# LEDSubMatrixHighDensity_v2.net
KiCad netlist of a schematic drawn in EAGLE
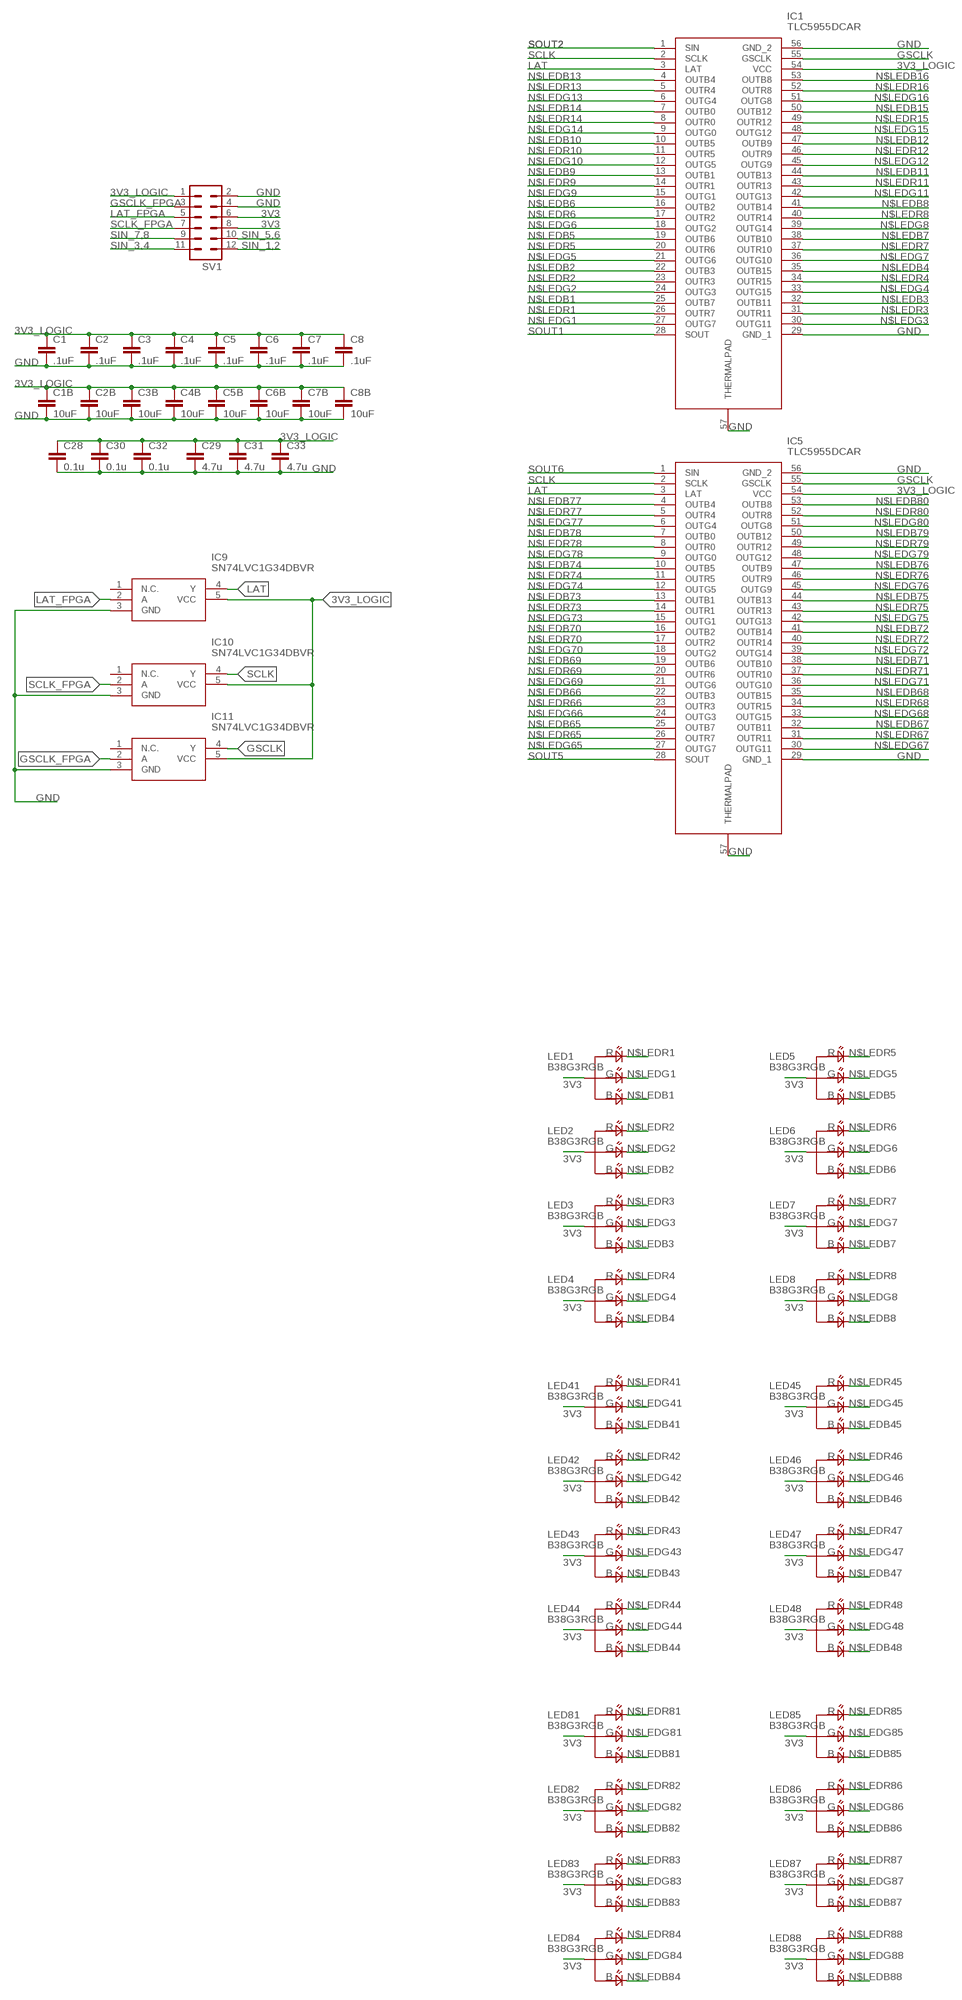
[diagram p0: schematic, sheet 1, part 1 of 2]
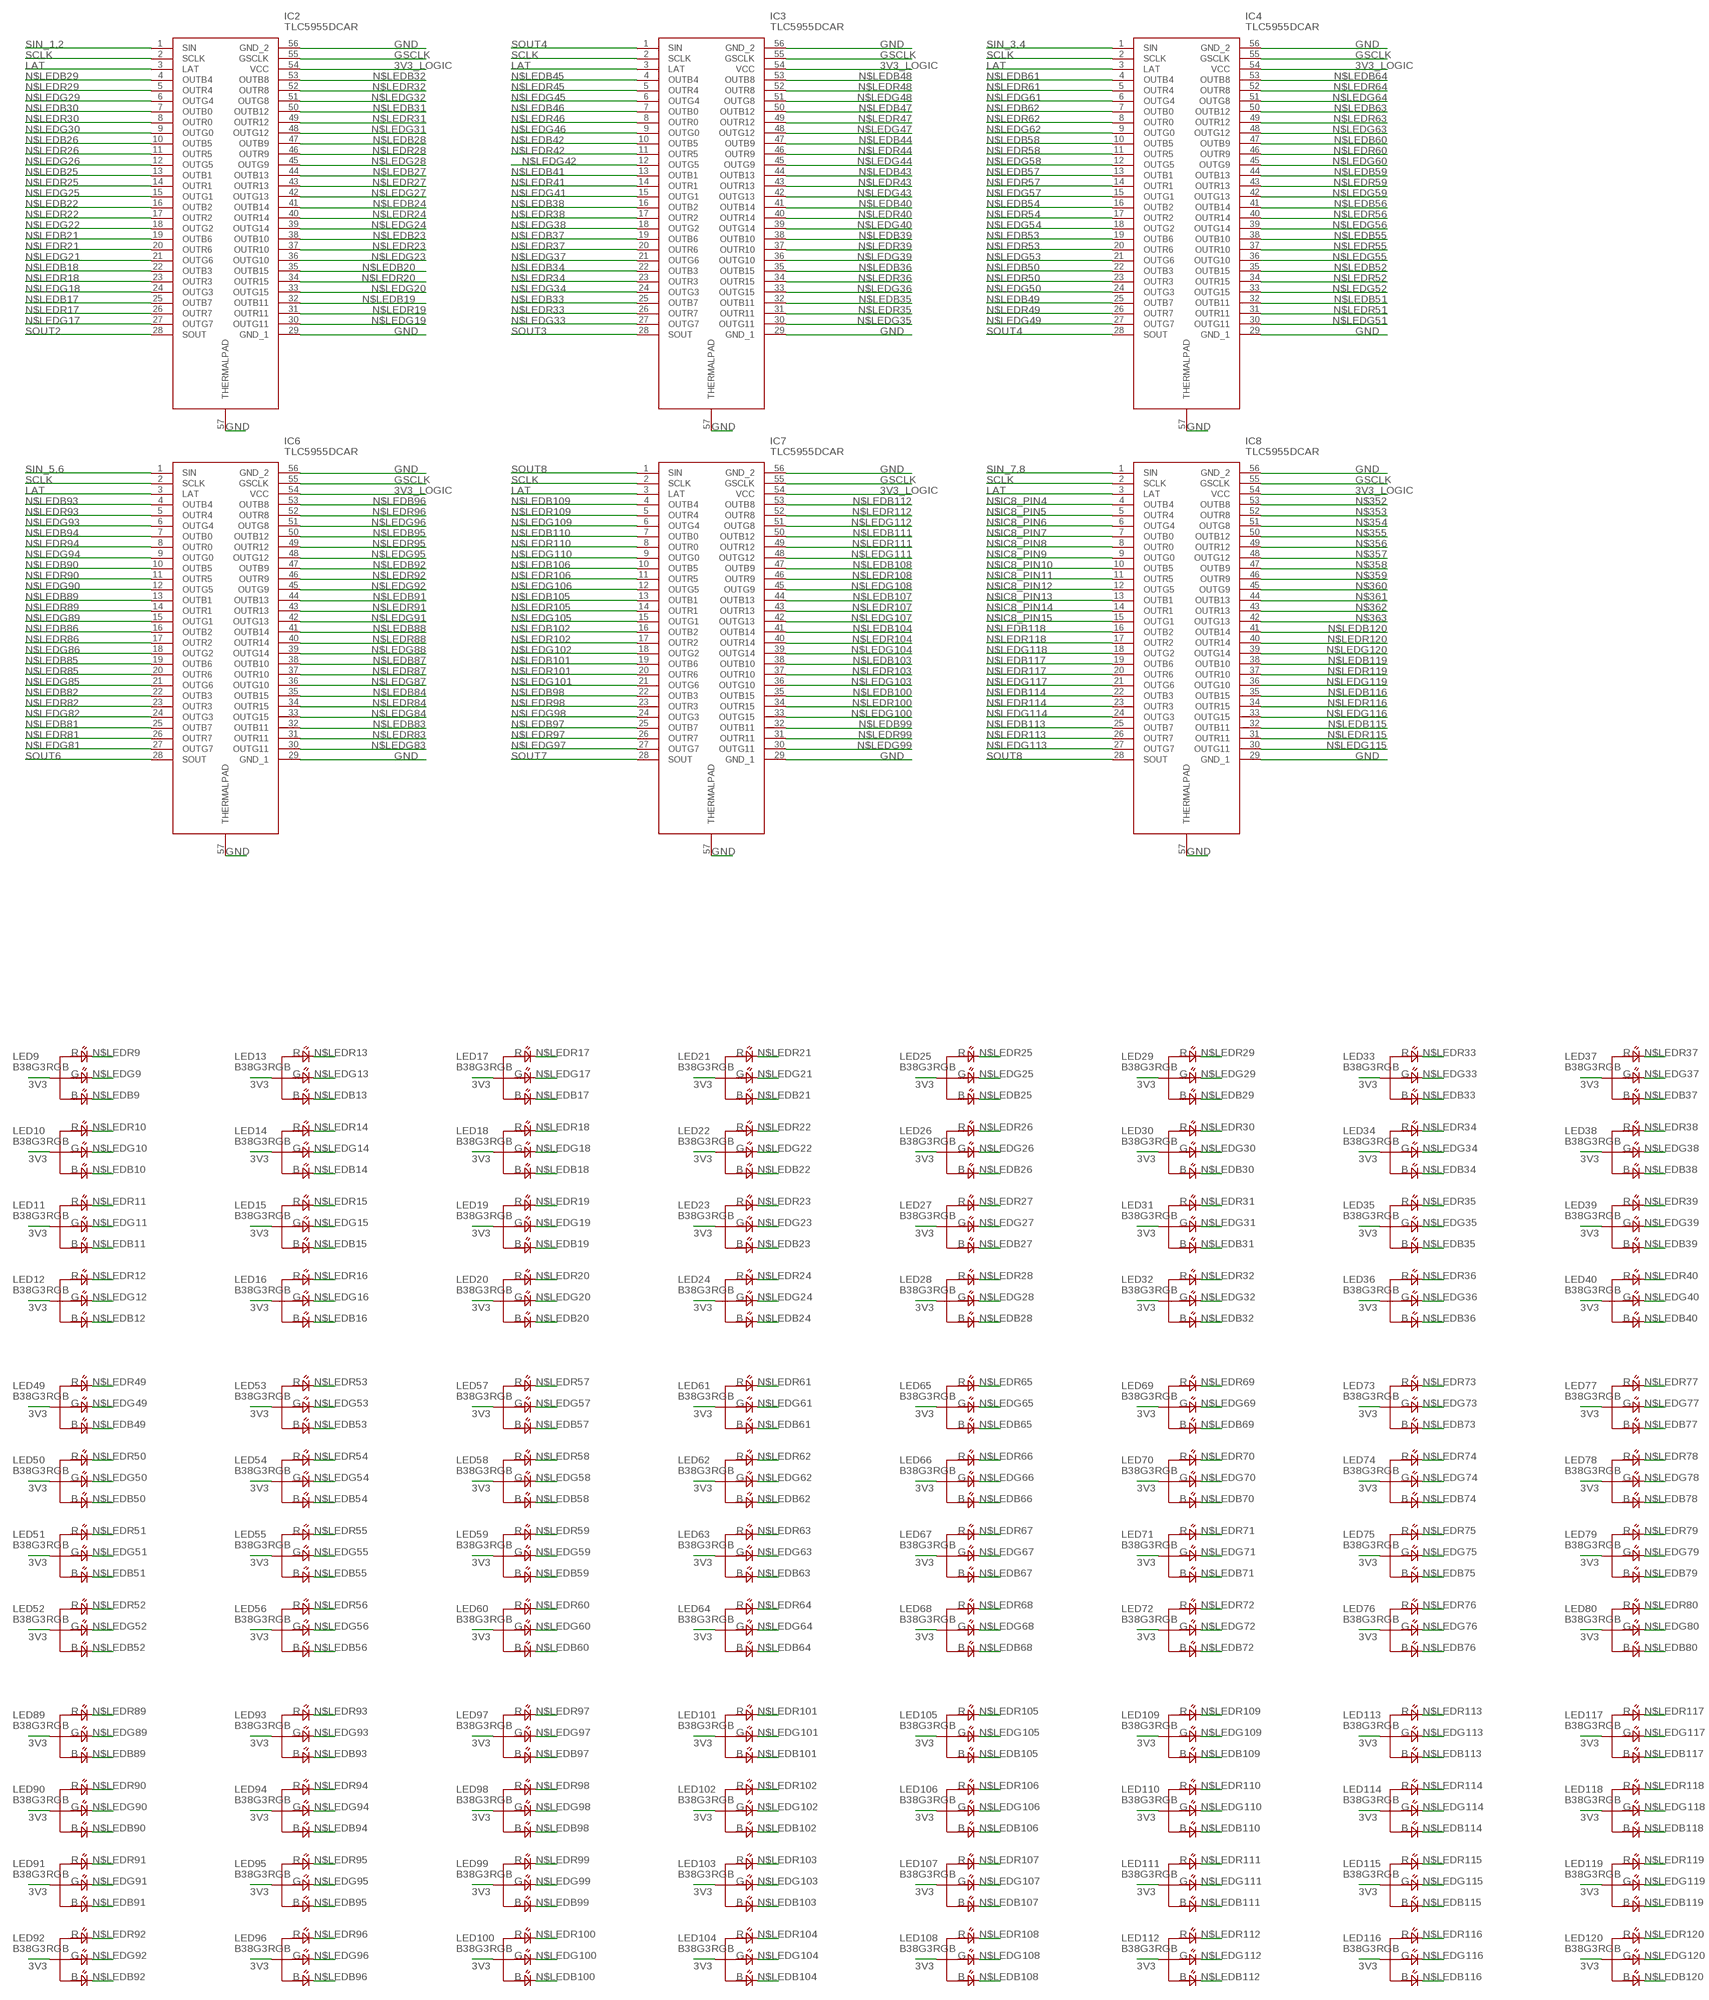
[diagram p1: schematic, sheet 1, part 2 of 2]

(export (version "E")
  (design (tool "Eeschema 10.0.6"))
  (components
    (comp (ref "C1")
      (value ".1uF")
      (footprint "eagle-import:C0402")
      (libsource (lib "eagle-import") (part "C-EUC0402"))
    )
    (comp (ref "C1B")
      (value "10uF")
      (footprint "eagle-import:C0402")
      (libsource (lib "eagle-import") (part "C-EUC0402"))
    )
    (comp (ref "C2")
      (value ".1uF")
      (footprint "eagle-import:C0402")
      (libsource (lib "eagle-import") (part "C-EUC0402"))
    )
    (comp (ref "C2B")
      (value "10uF")
      (footprint "eagle-import:C0402")
      (libsource (lib "eagle-import") (part "C-EUC0402"))
    )
    (comp (ref "C3")
      (value ".1uF")
      (footprint "eagle-import:C0402")
      (libsource (lib "eagle-import") (part "C-EUC0402"))
    )
    (comp (ref "C3B")
      (value "10uF")
      (footprint "eagle-import:C0402")
      (libsource (lib "eagle-import") (part "C-EUC0402"))
    )
    (comp (ref "C4")
      (value ".1uF")
      (footprint "eagle-import:C0402")
      (libsource (lib "eagle-import") (part "C-EUC0402"))
    )
    (comp (ref "C4B")
      (value "10uF")
      (footprint "eagle-import:C0402")
      (libsource (lib "eagle-import") (part "C-EUC0402"))
    )
    (comp (ref "C5")
      (value ".1uF")
      (footprint "eagle-import:C0402")
      (libsource (lib "eagle-import") (part "C-EUC0402"))
    )
    (comp (ref "C5B")
      (value "10uF")
      (footprint "eagle-import:C0402")
      (libsource (lib "eagle-import") (part "C-EUC0402"))
    )
    (comp (ref "C6")
      (value ".1uF")
      (footprint "eagle-import:C0402")
      (libsource (lib "eagle-import") (part "C-EUC0402"))
    )
    (comp (ref "C6B")
      (value "10uF")
      (footprint "eagle-import:C0402")
      (libsource (lib "eagle-import") (part "C-EUC0402"))
    )
    (comp (ref "C7")
      (value ".1uF")
      (footprint "eagle-import:C0402")
      (libsource (lib "eagle-import") (part "C-EUC0402"))
    )
    (comp (ref "C7B")
      (value "10uF")
      (footprint "eagle-import:C0402")
      (libsource (lib "eagle-import") (part "C-EUC0402"))
    )
    (comp (ref "C8")
      (value ".1uF")
      (footprint "eagle-import:C0402")
      (libsource (lib "eagle-import") (part "C-EUC0402"))
    )
    (comp (ref "C8B")
      (value "10uF")
      (footprint "eagle-import:C0402")
      (libsource (lib "eagle-import") (part "C-EUC0402"))
    )
    (comp (ref "C28")
      (value "0.1u")
      (footprint "eagle-import:C0402")
      (libsource (lib "eagle-import") (part "C-EUC0402"))
    )
    (comp (ref "C29")
      (value "4.7u")
      (footprint "eagle-import:C0402")
      (libsource (lib "eagle-import") (part "C-EUC0402"))
    )
    (comp (ref "C30")
      (value "0.1u")
      (footprint "eagle-import:C0402")
      (libsource (lib "eagle-import") (part "C-EUC0402"))
    )
    (comp (ref "C31")
      (value "4.7u")
      (footprint "eagle-import:C0402")
      (libsource (lib "eagle-import") (part "C-EUC0402"))
    )
    (comp (ref "C32")
      (value "0.1u")
      (footprint "eagle-import:C0402")
      (libsource (lib "eagle-import") (part "C-EUC0402"))
    )
    (comp (ref "C33")
      (value "4.7u")
      (footprint "eagle-import:C0402")
      (libsource (lib "eagle-import") (part "C-EUC0402"))
    )
    (comp (ref "IC1")
      (value "TLC5955DCAR")
      (footprint "eagle-import:SOP50P810X120-57N")
      (fields (field (name "MOUSER_PART_NUMBER") "595-TLC5955DCAR"))
      (libsource (lib "eagle-import") (part "TLC5955DCAR"))
    )
    (comp (ref "IC2")
      (value "TLC5955DCAR")
      (footprint "eagle-import:SOP50P810X120-57N")
      (fields (field (name "MOUSER_PART_NUMBER") "595-TLC5955DCAR"))
      (libsource (lib "eagle-import") (part "TLC5955DCAR"))
    )
    (comp (ref "IC3")
      (value "TLC5955DCAR")
      (footprint "eagle-import:SOP50P810X120-57N")
      (fields (field (name "MOUSER_PART_NUMBER") "595-TLC5955DCAR"))
      (libsource (lib "eagle-import") (part "TLC5955DCAR"))
    )
    (comp (ref "IC4")
      (value "TLC5955DCAR")
      (footprint "eagle-import:SOP50P810X120-57N")
      (fields (field (name "MOUSER_PART_NUMBER") "595-TLC5955DCAR"))
      (libsource (lib "eagle-import") (part "TLC5955DCAR"))
    )
    (comp (ref "IC5")
      (value "TLC5955DCAR")
      (footprint "eagle-import:SOP50P810X120-57N")
      (fields (field (name "MOUSER_PART_NUMBER") "595-TLC5955DCAR"))
      (libsource (lib "eagle-import") (part "TLC5955DCAR"))
    )
    (comp (ref "IC6")
      (value "TLC5955DCAR")
      (footprint "eagle-import:SOP50P810X120-57N")
      (fields (field (name "MOUSER_PART_NUMBER") "595-TLC5955DCAR"))
      (libsource (lib "eagle-import") (part "TLC5955DCAR"))
    )
    (comp (ref "IC7")
      (value "TLC5955DCAR")
      (footprint "eagle-import:SOP50P810X120-57N")
      (fields (field (name "MOUSER_PART_NUMBER") "595-TLC5955DCAR"))
      (libsource (lib "eagle-import") (part "TLC5955DCAR"))
    )
    (comp (ref "IC8")
      (value "TLC5955DCAR")
      (footprint "eagle-import:SOP50P810X120-57N")
      (fields (field (name "MOUSER_PART_NUMBER") "595-TLC5955DCAR"))
      (libsource (lib "eagle-import") (part "TLC5955DCAR"))
    )
    (comp (ref "IC9")
      (value "SN74LVC1G34DBVR")
      (footprint "eagle-import:SOT95P280X145-5N")
      (fields (field (name "MOUSER_PART_NUMBER") "595-SN74LVC1G34DBVR"))
      (libsource (lib "eagle-import") (part "SN74LVC1G34DBVR"))
    )
    (comp (ref "IC10")
      (value "SN74LVC1G34DBVR")
      (footprint "eagle-import:SOT95P280X145-5N")
      (fields (field (name "MOUSER_PART_NUMBER") "595-SN74LVC1G34DBVR"))
      (libsource (lib "eagle-import") (part "SN74LVC1G34DBVR"))
    )
    (comp (ref "IC11")
      (value "SN74LVC1G34DBVR")
      (footprint "eagle-import:SOT95P280X145-5N")
      (fields (field (name "MOUSER_PART_NUMBER") "595-SN74LVC1G34DBVR"))
      (libsource (lib "eagle-import") (part "SN74LVC1G34DBVR"))
    )
    (comp (ref "LED1")
      (value "B38G3RGB")
      (footprint "eagle-import:B38G3RGB")
      (fields
        (field (name "ARROW_PART_NUMBER") "SML-LX0606IGC-TR")
        (field (name "MOUSER_PART_NUMBER") "696-SML-0606IGCTR")
      )
      (libsource (lib "eagle-import") (part "B38G3RGB"))
    )
    (comp (ref "LED2")
      (value "B38G3RGB")
      (footprint "eagle-import:B38G3RGB")
      (fields
        (field (name "ARROW_PART_NUMBER") "SML-LX0606IGC-TR")
        (field (name "MOUSER_PART_NUMBER") "696-SML-0606IGCTR")
      )
      (libsource (lib "eagle-import") (part "B38G3RGB"))
    )
    (comp (ref "LED3")
      (value "B38G3RGB")
      (footprint "eagle-import:B38G3RGB")
      (fields
        (field (name "ARROW_PART_NUMBER") "SML-LX0606IGC-TR")
        (field (name "MOUSER_PART_NUMBER") "696-SML-0606IGCTR")
      )
      (libsource (lib "eagle-import") (part "B38G3RGB"))
    )
    (comp (ref "LED4")
      (value "B38G3RGB")
      (footprint "eagle-import:B38G3RGB")
      (fields
        (field (name "ARROW_PART_NUMBER") "SML-LX0606IGC-TR")
        (field (name "MOUSER_PART_NUMBER") "696-SML-0606IGCTR")
      )
      (libsource (lib "eagle-import") (part "B38G3RGB"))
    )
    (comp (ref "LED5")
      (value "B38G3RGB")
      (footprint "eagle-import:B38G3RGB")
      (fields
        (field (name "ARROW_PART_NUMBER") "SML-LX0606IGC-TR")
        (field (name "MOUSER_PART_NUMBER") "696-SML-0606IGCTR")
      )
      (libsource (lib "eagle-import") (part "B38G3RGB"))
    )
    (comp (ref "LED6")
      (value "B38G3RGB")
      (footprint "eagle-import:B38G3RGB")
      (fields
        (field (name "ARROW_PART_NUMBER") "SML-LX0606IGC-TR")
        (field (name "MOUSER_PART_NUMBER") "696-SML-0606IGCTR")
      )
      (libsource (lib "eagle-import") (part "B38G3RGB"))
    )
    (comp (ref "LED7")
      (value "B38G3RGB")
      (footprint "eagle-import:B38G3RGB")
      (fields
        (field (name "ARROW_PART_NUMBER") "SML-LX0606IGC-TR")
        (field (name "MOUSER_PART_NUMBER") "696-SML-0606IGCTR")
      )
      (libsource (lib "eagle-import") (part "B38G3RGB"))
    )
    (comp (ref "LED8")
      (value "B38G3RGB")
      (footprint "eagle-import:B38G3RGB")
      (fields
        (field (name "ARROW_PART_NUMBER") "SML-LX0606IGC-TR")
        (field (name "MOUSER_PART_NUMBER") "696-SML-0606IGCTR")
      )
      (libsource (lib "eagle-import") (part "B38G3RGB"))
    )
    (comp (ref "LED9")
      (value "B38G3RGB")
      (footprint "eagle-import:B38G3RGB")
      (fields
        (field (name "ARROW_PART_NUMBER") "SML-LX0606IGC-TR")
        (field (name "MOUSER_PART_NUMBER") "696-SML-0606IGCTR")
      )
      (libsource (lib "eagle-import") (part "B38G3RGB"))
    )
    (comp (ref "LED10")
      (value "B38G3RGB")
      (footprint "eagle-import:B38G3RGB")
      (fields
        (field (name "ARROW_PART_NUMBER") "SML-LX0606IGC-TR")
        (field (name "MOUSER_PART_NUMBER") "696-SML-0606IGCTR")
      )
      (libsource (lib "eagle-import") (part "B38G3RGB"))
    )
    (comp (ref "LED11")
      (value "B38G3RGB")
      (footprint "eagle-import:B38G3RGB")
      (fields
        (field (name "ARROW_PART_NUMBER") "SML-LX0606IGC-TR")
        (field (name "MOUSER_PART_NUMBER") "696-SML-0606IGCTR")
      )
      (libsource (lib "eagle-import") (part "B38G3RGB"))
    )
    (comp (ref "LED12")
      (value "B38G3RGB")
      (footprint "eagle-import:B38G3RGB")
      (fields
        (field (name "ARROW_PART_NUMBER") "SML-LX0606IGC-TR")
        (field (name "MOUSER_PART_NUMBER") "696-SML-0606IGCTR")
      )
      (libsource (lib "eagle-import") (part "B38G3RGB"))
    )
    (comp (ref "LED13")
      (value "B38G3RGB")
      (footprint "eagle-import:B38G3RGB")
      (fields
        (field (name "ARROW_PART_NUMBER") "SML-LX0606IGC-TR")
        (field (name "MOUSER_PART_NUMBER") "696-SML-0606IGCTR")
      )
      (libsource (lib "eagle-import") (part "B38G3RGB"))
    )
    (comp (ref "LED14")
      (value "B38G3RGB")
      (footprint "eagle-import:B38G3RGB")
      (fields
        (field (name "ARROW_PART_NUMBER") "SML-LX0606IGC-TR")
        (field (name "MOUSER_PART_NUMBER") "696-SML-0606IGCTR")
      )
      (libsource (lib "eagle-import") (part "B38G3RGB"))
    )
    (comp (ref "LED15")
      (value "B38G3RGB")
      (footprint "eagle-import:B38G3RGB")
      (fields
        (field (name "ARROW_PART_NUMBER") "SML-LX0606IGC-TR")
        (field (name "MOUSER_PART_NUMBER") "696-SML-0606IGCTR")
      )
      (libsource (lib "eagle-import") (part "B38G3RGB"))
    )
    (comp (ref "LED16")
      (value "B38G3RGB")
      (footprint "eagle-import:B38G3RGB")
      (fields
        (field (name "ARROW_PART_NUMBER") "SML-LX0606IGC-TR")
        (field (name "MOUSER_PART_NUMBER") "696-SML-0606IGCTR")
      )
      (libsource (lib "eagle-import") (part "B38G3RGB"))
    )
    (comp (ref "LED17")
      (value "B38G3RGB")
      (footprint "eagle-import:B38G3RGB")
      (fields
        (field (name "ARROW_PART_NUMBER") "SML-LX0606IGC-TR")
        (field (name "MOUSER_PART_NUMBER") "696-SML-0606IGCTR")
      )
      (libsource (lib "eagle-import") (part "B38G3RGB"))
    )
    (comp (ref "LED18")
      (value "B38G3RGB")
      (footprint "eagle-import:B38G3RGB")
      (fields
        (field (name "ARROW_PART_NUMBER") "SML-LX0606IGC-TR")
        (field (name "MOUSER_PART_NUMBER") "696-SML-0606IGCTR")
      )
      (libsource (lib "eagle-import") (part "B38G3RGB"))
    )
    (comp (ref "LED19")
      (value "B38G3RGB")
      (footprint "eagle-import:B38G3RGB")
      (fields
        (field (name "ARROW_PART_NUMBER") "SML-LX0606IGC-TR")
        (field (name "MOUSER_PART_NUMBER") "696-SML-0606IGCTR")
      )
      (libsource (lib "eagle-import") (part "B38G3RGB"))
    )
    (comp (ref "LED20")
      (value "B38G3RGB")
      (footprint "eagle-import:B38G3RGB")
      (fields
        (field (name "ARROW_PART_NUMBER") "SML-LX0606IGC-TR")
        (field (name "MOUSER_PART_NUMBER") "696-SML-0606IGCTR")
      )
      (libsource (lib "eagle-import") (part "B38G3RGB"))
    )
    (comp (ref "LED21")
      (value "B38G3RGB")
      (footprint "eagle-import:B38G3RGB")
      (fields
        (field (name "ARROW_PART_NUMBER") "SML-LX0606IGC-TR")
        (field (name "MOUSER_PART_NUMBER") "696-SML-0606IGCTR")
      )
      (libsource (lib "eagle-import") (part "B38G3RGB"))
    )
    (comp (ref "LED22")
      (value "B38G3RGB")
      (footprint "eagle-import:B38G3RGB")
      (fields
        (field (name "ARROW_PART_NUMBER") "SML-LX0606IGC-TR")
        (field (name "MOUSER_PART_NUMBER") "696-SML-0606IGCTR")
      )
      (libsource (lib "eagle-import") (part "B38G3RGB"))
    )
    (comp (ref "LED23")
      (value "B38G3RGB")
      (footprint "eagle-import:B38G3RGB")
      (fields
        (field (name "ARROW_PART_NUMBER") "SML-LX0606IGC-TR")
        (field (name "MOUSER_PART_NUMBER") "696-SML-0606IGCTR")
      )
      (libsource (lib "eagle-import") (part "B38G3RGB"))
    )
    (comp (ref "LED24")
      (value "B38G3RGB")
      (footprint "eagle-import:B38G3RGB")
      (fields
        (field (name "ARROW_PART_NUMBER") "SML-LX0606IGC-TR")
        (field (name "MOUSER_PART_NUMBER") "696-SML-0606IGCTR")
      )
      (libsource (lib "eagle-import") (part "B38G3RGB"))
    )
    (comp (ref "LED25")
      (value "B38G3RGB")
      (footprint "eagle-import:B38G3RGB")
      (fields
        (field (name "ARROW_PART_NUMBER") "SML-LX0606IGC-TR")
        (field (name "MOUSER_PART_NUMBER") "696-SML-0606IGCTR")
      )
      (libsource (lib "eagle-import") (part "B38G3RGB"))
    )
    (comp (ref "LED26")
      (value "B38G3RGB")
      (footprint "eagle-import:B38G3RGB")
      (fields
        (field (name "ARROW_PART_NUMBER") "SML-LX0606IGC-TR")
        (field (name "MOUSER_PART_NUMBER") "696-SML-0606IGCTR")
      )
      (libsource (lib "eagle-import") (part "B38G3RGB"))
    )
    (comp (ref "LED27")
      (value "B38G3RGB")
      (footprint "eagle-import:B38G3RGB")
      (fields
        (field (name "ARROW_PART_NUMBER") "SML-LX0606IGC-TR")
        (field (name "MOUSER_PART_NUMBER") "696-SML-0606IGCTR")
      )
      (libsource (lib "eagle-import") (part "B38G3RGB"))
    )
    (comp (ref "LED28")
      (value "B38G3RGB")
      (footprint "eagle-import:B38G3RGB")
      (fields
        (field (name "ARROW_PART_NUMBER") "SML-LX0606IGC-TR")
        (field (name "MOUSER_PART_NUMBER") "696-SML-0606IGCTR")
      )
      (libsource (lib "eagle-import") (part "B38G3RGB"))
    )
    (comp (ref "LED29")
      (value "B38G3RGB")
      (footprint "eagle-import:B38G3RGB")
      (fields
        (field (name "ARROW_PART_NUMBER") "SML-LX0606IGC-TR")
        (field (name "MOUSER_PART_NUMBER") "696-SML-0606IGCTR")
      )
      (libsource (lib "eagle-import") (part "B38G3RGB"))
    )
    (comp (ref "LED30")
      (value "B38G3RGB")
      (footprint "eagle-import:B38G3RGB")
      (fields
        (field (name "ARROW_PART_NUMBER") "SML-LX0606IGC-TR")
        (field (name "MOUSER_PART_NUMBER") "696-SML-0606IGCTR")
      )
      (libsource (lib "eagle-import") (part "B38G3RGB"))
    )
    (comp (ref "LED31")
      (value "B38G3RGB")
      (footprint "eagle-import:B38G3RGB")
      (fields
        (field (name "ARROW_PART_NUMBER") "SML-LX0606IGC-TR")
        (field (name "MOUSER_PART_NUMBER") "696-SML-0606IGCTR")
      )
      (libsource (lib "eagle-import") (part "B38G3RGB"))
    )
    (comp (ref "LED32")
      (value "B38G3RGB")
      (footprint "eagle-import:B38G3RGB")
      (fields
        (field (name "ARROW_PART_NUMBER") "SML-LX0606IGC-TR")
        (field (name "MOUSER_PART_NUMBER") "696-SML-0606IGCTR")
      )
      (libsource (lib "eagle-import") (part "B38G3RGB"))
    )
    (comp (ref "LED33")
      (value "B38G3RGB")
      (footprint "eagle-import:B38G3RGB")
      (fields
        (field (name "ARROW_PART_NUMBER") "SML-LX0606IGC-TR")
        (field (name "MOUSER_PART_NUMBER") "696-SML-0606IGCTR")
      )
      (libsource (lib "eagle-import") (part "B38G3RGB"))
    )
    (comp (ref "LED34")
      (value "B38G3RGB")
      (footprint "eagle-import:B38G3RGB")
      (fields
        (field (name "ARROW_PART_NUMBER") "SML-LX0606IGC-TR")
        (field (name "MOUSER_PART_NUMBER") "696-SML-0606IGCTR")
      )
      (libsource (lib "eagle-import") (part "B38G3RGB"))
    )
    (comp (ref "LED35")
      (value "B38G3RGB")
      (footprint "eagle-import:B38G3RGB")
      (fields
        (field (name "ARROW_PART_NUMBER") "SML-LX0606IGC-TR")
        (field (name "MOUSER_PART_NUMBER") "696-SML-0606IGCTR")
      )
      (libsource (lib "eagle-import") (part "B38G3RGB"))
    )
    (comp (ref "LED36")
      (value "B38G3RGB")
      (footprint "eagle-import:B38G3RGB")
      (fields
        (field (name "ARROW_PART_NUMBER") "SML-LX0606IGC-TR")
        (field (name "MOUSER_PART_NUMBER") "696-SML-0606IGCTR")
      )
      (libsource (lib "eagle-import") (part "B38G3RGB"))
    )
    (comp (ref "LED37")
      (value "B38G3RGB")
      (footprint "eagle-import:B38G3RGB")
      (fields
        (field (name "ARROW_PART_NUMBER") "SML-LX0606IGC-TR")
        (field (name "MOUSER_PART_NUMBER") "696-SML-0606IGCTR")
      )
      (libsource (lib "eagle-import") (part "B38G3RGB"))
    )
    (comp (ref "LED38")
      (value "B38G3RGB")
      (footprint "eagle-import:B38G3RGB")
      (fields
        (field (name "ARROW_PART_NUMBER") "SML-LX0606IGC-TR")
        (field (name "MOUSER_PART_NUMBER") "696-SML-0606IGCTR")
      )
      (libsource (lib "eagle-import") (part "B38G3RGB"))
    )
    (comp (ref "LED39")
      (value "B38G3RGB")
      (footprint "eagle-import:B38G3RGB")
      (fields
        (field (name "ARROW_PART_NUMBER") "SML-LX0606IGC-TR")
        (field (name "MOUSER_PART_NUMBER") "696-SML-0606IGCTR")
      )
      (libsource (lib "eagle-import") (part "B38G3RGB"))
    )
    (comp (ref "LED40")
      (value "B38G3RGB")
      (footprint "eagle-import:B38G3RGB")
      (fields
        (field (name "ARROW_PART_NUMBER") "SML-LX0606IGC-TR")
        (field (name "MOUSER_PART_NUMBER") "696-SML-0606IGCTR")
      )
      (libsource (lib "eagle-import") (part "B38G3RGB"))
    )
    (comp (ref "LED41")
      (value "B38G3RGB")
      (footprint "eagle-import:B38G3RGB")
      (fields
        (field (name "ARROW_PART_NUMBER") "SML-LX0606IGC-TR")
        (field (name "MOUSER_PART_NUMBER") "696-SML-0606IGCTR")
      )
      (libsource (lib "eagle-import") (part "B38G3RGB"))
    )
    (comp (ref "LED42")
      (value "B38G3RGB")
      (footprint "eagle-import:B38G3RGB")
      (fields
        (field (name "ARROW_PART_NUMBER") "SML-LX0606IGC-TR")
        (field (name "MOUSER_PART_NUMBER") "696-SML-0606IGCTR")
      )
      (libsource (lib "eagle-import") (part "B38G3RGB"))
    )
    (comp (ref "LED43")
      (value "B38G3RGB")
      (footprint "eagle-import:B38G3RGB")
      (fields
        (field (name "ARROW_PART_NUMBER") "SML-LX0606IGC-TR")
        (field (name "MOUSER_PART_NUMBER") "696-SML-0606IGCTR")
      )
      (libsource (lib "eagle-import") (part "B38G3RGB"))
    )
    (comp (ref "LED44")
      (value "B38G3RGB")
      (footprint "eagle-import:B38G3RGB")
      (fields
        (field (name "ARROW_PART_NUMBER") "SML-LX0606IGC-TR")
        (field (name "MOUSER_PART_NUMBER") "696-SML-0606IGCTR")
      )
      (libsource (lib "eagle-import") (part "B38G3RGB"))
    )
    (comp (ref "LED45")
      (value "B38G3RGB")
      (footprint "eagle-import:B38G3RGB")
      (fields
        (field (name "ARROW_PART_NUMBER") "SML-LX0606IGC-TR")
        (field (name "MOUSER_PART_NUMBER") "696-SML-0606IGCTR")
      )
      (libsource (lib "eagle-import") (part "B38G3RGB"))
    )
    (comp (ref "LED46")
      (value "B38G3RGB")
      (footprint "eagle-import:B38G3RGB")
      (fields
        (field (name "ARROW_PART_NUMBER") "SML-LX0606IGC-TR")
        (field (name "MOUSER_PART_NUMBER") "696-SML-0606IGCTR")
      )
      (libsource (lib "eagle-import") (part "B38G3RGB"))
    )
    (comp (ref "LED47")
      (value "B38G3RGB")
      (footprint "eagle-import:B38G3RGB")
      (fields
        (field (name "ARROW_PART_NUMBER") "SML-LX0606IGC-TR")
        (field (name "MOUSER_PART_NUMBER") "696-SML-0606IGCTR")
      )
      (libsource (lib "eagle-import") (part "B38G3RGB"))
    )
    (comp (ref "LED48")
      (value "B38G3RGB")
      (footprint "eagle-import:B38G3RGB")
      (fields
        (field (name "ARROW_PART_NUMBER") "SML-LX0606IGC-TR")
        (field (name "MOUSER_PART_NUMBER") "696-SML-0606IGCTR")
      )
      (libsource (lib "eagle-import") (part "B38G3RGB"))
    )
    (comp (ref "LED49")
      (value "B38G3RGB")
      (footprint "eagle-import:B38G3RGB")
      (fields
        (field (name "ARROW_PART_NUMBER") "SML-LX0606IGC-TR")
        (field (name "MOUSER_PART_NUMBER") "696-SML-0606IGCTR")
      )
      (libsource (lib "eagle-import") (part "B38G3RGB"))
    )
    (comp (ref "LED50")
      (value "B38G3RGB")
      (footprint "eagle-import:B38G3RGB")
      (fields
        (field (name "ARROW_PART_NUMBER") "SML-LX0606IGC-TR")
        (field (name "MOUSER_PART_NUMBER") "696-SML-0606IGCTR")
      )
      (libsource (lib "eagle-import") (part "B38G3RGB"))
    )
    (comp (ref "LED51")
      (value "B38G3RGB")
      (footprint "eagle-import:B38G3RGB")
      (fields
        (field (name "ARROW_PART_NUMBER") "SML-LX0606IGC-TR")
        (field (name "MOUSER_PART_NUMBER") "696-SML-0606IGCTR")
      )
      (libsource (lib "eagle-import") (part "B38G3RGB"))
    )
    (comp (ref "LED52")
      (value "B38G3RGB")
      (footprint "eagle-import:B38G3RGB")
      (fields
        (field (name "ARROW_PART_NUMBER") "SML-LX0606IGC-TR")
        (field (name "MOUSER_PART_NUMBER") "696-SML-0606IGCTR")
      )
      (libsource (lib "eagle-import") (part "B38G3RGB"))
    )
    (comp (ref "LED53")
      (value "B38G3RGB")
      (footprint "eagle-import:B38G3RGB")
      (fields
        (field (name "ARROW_PART_NUMBER") "SML-LX0606IGC-TR")
        (field (name "MOUSER_PART_NUMBER") "696-SML-0606IGCTR")
      )
      (libsource (lib "eagle-import") (part "B38G3RGB"))
    )
    (comp (ref "LED54")
      (value "B38G3RGB")
      (footprint "eagle-import:B38G3RGB")
      (fields
        (field (name "ARROW_PART_NUMBER") "SML-LX0606IGC-TR")
        (field (name "MOUSER_PART_NUMBER") "696-SML-0606IGCTR")
      )
      (libsource (lib "eagle-import") (part "B38G3RGB"))
    )
    (comp (ref "LED55")
      (value "B38G3RGB")
      (footprint "eagle-import:B38G3RGB")
      (fields
        (field (name "ARROW_PART_NUMBER") "SML-LX0606IGC-TR")
        (field (name "MOUSER_PART_NUMBER") "696-SML-0606IGCTR")
      )
      (libsource (lib "eagle-import") (part "B38G3RGB"))
    )
    (comp (ref "LED56")
      (value "B38G3RGB")
      (footprint "eagle-import:B38G3RGB")
      (fields
        (field (name "ARROW_PART_NUMBER") "SML-LX0606IGC-TR")
        (field (name "MOUSER_PART_NUMBER") "696-SML-0606IGCTR")
      )
      (libsource (lib "eagle-import") (part "B38G3RGB"))
    )
    (comp (ref "LED57")
      (value "B38G3RGB")
      (footprint "eagle-import:B38G3RGB")
      (fields
        (field (name "ARROW_PART_NUMBER") "SML-LX0606IGC-TR")
        (field (name "MOUSER_PART_NUMBER") "696-SML-0606IGCTR")
      )
      (libsource (lib "eagle-import") (part "B38G3RGB"))
    )
    (comp (ref "LED58")
      (value "B38G3RGB")
      (footprint "eagle-import:B38G3RGB")
      (fields
        (field (name "ARROW_PART_NUMBER") "SML-LX0606IGC-TR")
        (field (name "MOUSER_PART_NUMBER") "696-SML-0606IGCTR")
      )
      (libsource (lib "eagle-import") (part "B38G3RGB"))
    )
    (comp (ref "LED59")
      (value "B38G3RGB")
      (footprint "eagle-import:B38G3RGB")
      (fields
        (field (name "ARROW_PART_NUMBER") "SML-LX0606IGC-TR")
        (field (name "MOUSER_PART_NUMBER") "696-SML-0606IGCTR")
      )
      (libsource (lib "eagle-import") (part "B38G3RGB"))
    )
    (comp (ref "LED60")
      (value "B38G3RGB")
      (footprint "eagle-import:B38G3RGB")
      (fields
        (field (name "ARROW_PART_NUMBER") "SML-LX0606IGC-TR")
        (field (name "MOUSER_PART_NUMBER") "696-SML-0606IGCTR")
      )
      (libsource (lib "eagle-import") (part "B38G3RGB"))
    )
    (comp (ref "LED61")
      (value "B38G3RGB")
      (footprint "eagle-import:B38G3RGB")
      (fields
        (field (name "ARROW_PART_NUMBER") "SML-LX0606IGC-TR")
        (field (name "MOUSER_PART_NUMBER") "696-SML-0606IGCTR")
      )
      (libsource (lib "eagle-import") (part "B38G3RGB"))
    )
    (comp (ref "LED62")
      (value "B38G3RGB")
      (footprint "eagle-import:B38G3RGB")
      (fields
        (field (name "ARROW_PART_NUMBER") "SML-LX0606IGC-TR")
        (field (name "MOUSER_PART_NUMBER") "696-SML-0606IGCTR")
      )
      (libsource (lib "eagle-import") (part "B38G3RGB"))
    )
    (comp (ref "LED63")
      (value "B38G3RGB")
      (footprint "eagle-import:B38G3RGB")
      (fields
        (field (name "ARROW_PART_NUMBER") "SML-LX0606IGC-TR")
        (field (name "MOUSER_PART_NUMBER") "696-SML-0606IGCTR")
      )
      (libsource (lib "eagle-import") (part "B38G3RGB"))
    )
    (comp (ref "LED64")
      (value "B38G3RGB")
      (footprint "eagle-import:B38G3RGB")
      (fields
        (field (name "ARROW_PART_NUMBER") "SML-LX0606IGC-TR")
        (field (name "MOUSER_PART_NUMBER") "696-SML-0606IGCTR")
      )
      (libsource (lib "eagle-import") (part "B38G3RGB"))
    )
    (comp (ref "LED65")
      (value "B38G3RGB")
      (footprint "eagle-import:B38G3RGB")
      (fields
        (field (name "ARROW_PART_NUMBER") "SML-LX0606IGC-TR")
        (field (name "MOUSER_PART_NUMBER") "696-SML-0606IGCTR")
      )
      (libsource (lib "eagle-import") (part "B38G3RGB"))
    )
    (comp (ref "LED66")
      (value "B38G3RGB")
      (footprint "eagle-import:B38G3RGB")
      (fields
        (field (name "ARROW_PART_NUMBER") "SML-LX0606IGC-TR")
        (field (name "MOUSER_PART_NUMBER") "696-SML-0606IGCTR")
      )
      (libsource (lib "eagle-import") (part "B38G3RGB"))
    )
    (comp (ref "LED67")
      (value "B38G3RGB")
      (footprint "eagle-import:B38G3RGB")
      (fields
        (field (name "ARROW_PART_NUMBER") "SML-LX0606IGC-TR")
        (field (name "MOUSER_PART_NUMBER") "696-SML-0606IGCTR")
      )
      (libsource (lib "eagle-import") (part "B38G3RGB"))
    )
    (comp (ref "LED68")
      (value "B38G3RGB")
      (footprint "eagle-import:B38G3RGB")
      (fields
        (field (name "ARROW_PART_NUMBER") "SML-LX0606IGC-TR")
        (field (name "MOUSER_PART_NUMBER") "696-SML-0606IGCTR")
      )
      (libsource (lib "eagle-import") (part "B38G3RGB"))
    )
    (comp (ref "LED69")
      (value "B38G3RGB")
      (footprint "eagle-import:B38G3RGB")
      (fields
        (field (name "ARROW_PART_NUMBER") "SML-LX0606IGC-TR")
        (field (name "MOUSER_PART_NUMBER") "696-SML-0606IGCTR")
      )
      (libsource (lib "eagle-import") (part "B38G3RGB"))
    )
    (comp (ref "LED70")
      (value "B38G3RGB")
      (footprint "eagle-import:B38G3RGB")
      (fields
        (field (name "ARROW_PART_NUMBER") "SML-LX0606IGC-TR")
        (field (name "MOUSER_PART_NUMBER") "696-SML-0606IGCTR")
      )
      (libsource (lib "eagle-import") (part "B38G3RGB"))
    )
    (comp (ref "LED71")
      (value "B38G3RGB")
      (footprint "eagle-import:B38G3RGB")
      (fields
        (field (name "ARROW_PART_NUMBER") "SML-LX0606IGC-TR")
        (field (name "MOUSER_PART_NUMBER") "696-SML-0606IGCTR")
      )
      (libsource (lib "eagle-import") (part "B38G3RGB"))
    )
    (comp (ref "LED72")
      (value "B38G3RGB")
      (footprint "eagle-import:B38G3RGB")
      (fields
        (field (name "ARROW_PART_NUMBER") "SML-LX0606IGC-TR")
        (field (name "MOUSER_PART_NUMBER") "696-SML-0606IGCTR")
      )
      (libsource (lib "eagle-import") (part "B38G3RGB"))
    )
    (comp (ref "LED73")
      (value "B38G3RGB")
      (footprint "eagle-import:B38G3RGB")
      (fields
        (field (name "ARROW_PART_NUMBER") "SML-LX0606IGC-TR")
        (field (name "MOUSER_PART_NUMBER") "696-SML-0606IGCTR")
      )
      (libsource (lib "eagle-import") (part "B38G3RGB"))
    )
    (comp (ref "LED74")
      (value "B38G3RGB")
      (footprint "eagle-import:B38G3RGB")
      (fields
        (field (name "ARROW_PART_NUMBER") "SML-LX0606IGC-TR")
        (field (name "MOUSER_PART_NUMBER") "696-SML-0606IGCTR")
      )
      (libsource (lib "eagle-import") (part "B38G3RGB"))
    )
    (comp (ref "LED75")
      (value "B38G3RGB")
      (footprint "eagle-import:B38G3RGB")
      (fields
        (field (name "ARROW_PART_NUMBER") "SML-LX0606IGC-TR")
        (field (name "MOUSER_PART_NUMBER") "696-SML-0606IGCTR")
      )
      (libsource (lib "eagle-import") (part "B38G3RGB"))
    )
    (comp (ref "LED76")
      (value "B38G3RGB")
      (footprint "eagle-import:B38G3RGB")
      (fields
        (field (name "ARROW_PART_NUMBER") "SML-LX0606IGC-TR")
        (field (name "MOUSER_PART_NUMBER") "696-SML-0606IGCTR")
      )
      (libsource (lib "eagle-import") (part "B38G3RGB"))
    )
    (comp (ref "LED77")
      (value "B38G3RGB")
      (footprint "eagle-import:B38G3RGB")
      (fields
        (field (name "ARROW_PART_NUMBER") "SML-LX0606IGC-TR")
        (field (name "MOUSER_PART_NUMBER") "696-SML-0606IGCTR")
      )
      (libsource (lib "eagle-import") (part "B38G3RGB"))
    )
    (comp (ref "LED78")
      (value "B38G3RGB")
      (footprint "eagle-import:B38G3RGB")
      (fields
        (field (name "ARROW_PART_NUMBER") "SML-LX0606IGC-TR")
        (field (name "MOUSER_PART_NUMBER") "696-SML-0606IGCTR")
      )
      (libsource (lib "eagle-import") (part "B38G3RGB"))
    )
    (comp (ref "LED79")
      (value "B38G3RGB")
      (footprint "eagle-import:B38G3RGB")
      (fields
        (field (name "ARROW_PART_NUMBER") "SML-LX0606IGC-TR")
        (field (name "MOUSER_PART_NUMBER") "696-SML-0606IGCTR")
      )
      (libsource (lib "eagle-import") (part "B38G3RGB"))
    )
    (comp (ref "LED80")
      (value "B38G3RGB")
      (footprint "eagle-import:B38G3RGB")
      (fields
        (field (name "ARROW_PART_NUMBER") "SML-LX0606IGC-TR")
        (field (name "MOUSER_PART_NUMBER") "696-SML-0606IGCTR")
      )
      (libsource (lib "eagle-import") (part "B38G3RGB"))
    )
    (comp (ref "LED81")
      (value "B38G3RGB")
      (footprint "eagle-import:B38G3RGB")
      (fields
        (field (name "ARROW_PART_NUMBER") "SML-LX0606IGC-TR")
        (field (name "MOUSER_PART_NUMBER") "696-SML-0606IGCTR")
      )
      (libsource (lib "eagle-import") (part "B38G3RGB"))
    )
    (comp (ref "LED82")
      (value "B38G3RGB")
      (footprint "eagle-import:B38G3RGB")
      (fields
        (field (name "ARROW_PART_NUMBER") "SML-LX0606IGC-TR")
        (field (name "MOUSER_PART_NUMBER") "696-SML-0606IGCTR")
      )
      (libsource (lib "eagle-import") (part "B38G3RGB"))
    )
    (comp (ref "LED83")
      (value "B38G3RGB")
      (footprint "eagle-import:B38G3RGB")
      (fields
        (field (name "ARROW_PART_NUMBER") "SML-LX0606IGC-TR")
        (field (name "MOUSER_PART_NUMBER") "696-SML-0606IGCTR")
      )
      (libsource (lib "eagle-import") (part "B38G3RGB"))
    )
    (comp (ref "LED84")
      (value "B38G3RGB")
      (footprint "eagle-import:B38G3RGB")
      (fields
        (field (name "ARROW_PART_NUMBER") "SML-LX0606IGC-TR")
        (field (name "MOUSER_PART_NUMBER") "696-SML-0606IGCTR")
      )
      (libsource (lib "eagle-import") (part "B38G3RGB"))
    )
    (comp (ref "LED85")
      (value "B38G3RGB")
      (footprint "eagle-import:B38G3RGB")
      (fields
        (field (name "ARROW_PART_NUMBER") "SML-LX0606IGC-TR")
        (field (name "MOUSER_PART_NUMBER") "696-SML-0606IGCTR")
      )
      (libsource (lib "eagle-import") (part "B38G3RGB"))
    )
    (comp (ref "LED86")
      (value "B38G3RGB")
      (footprint "eagle-import:B38G3RGB")
      (fields
        (field (name "ARROW_PART_NUMBER") "SML-LX0606IGC-TR")
        (field (name "MOUSER_PART_NUMBER") "696-SML-0606IGCTR")
      )
      (libsource (lib "eagle-import") (part "B38G3RGB"))
    )
    (comp (ref "LED87")
      (value "B38G3RGB")
      (footprint "eagle-import:B38G3RGB")
      (fields
        (field (name "ARROW_PART_NUMBER") "SML-LX0606IGC-TR")
        (field (name "MOUSER_PART_NUMBER") "696-SML-0606IGCTR")
      )
      (libsource (lib "eagle-import") (part "B38G3RGB"))
    )
    (comp (ref "LED88")
      (value "B38G3RGB")
      (footprint "eagle-import:B38G3RGB")
      (fields
        (field (name "ARROW_PART_NUMBER") "SML-LX0606IGC-TR")
        (field (name "MOUSER_PART_NUMBER") "696-SML-0606IGCTR")
      )
      (libsource (lib "eagle-import") (part "B38G3RGB"))
    )
    (comp (ref "LED89")
      (value "B38G3RGB")
      (footprint "eagle-import:B38G3RGB")
      (fields
        (field (name "ARROW_PART_NUMBER") "SML-LX0606IGC-TR")
        (field (name "MOUSER_PART_NUMBER") "696-SML-0606IGCTR")
      )
      (libsource (lib "eagle-import") (part "B38G3RGB"))
    )
    (comp (ref "LED90")
      (value "B38G3RGB")
      (footprint "eagle-import:B38G3RGB")
      (fields
        (field (name "ARROW_PART_NUMBER") "SML-LX0606IGC-TR")
        (field (name "MOUSER_PART_NUMBER") "696-SML-0606IGCTR")
      )
      (libsource (lib "eagle-import") (part "B38G3RGB"))
    )
    (comp (ref "LED91")
      (value "B38G3RGB")
      (footprint "eagle-import:B38G3RGB")
      (fields
        (field (name "ARROW_PART_NUMBER") "SML-LX0606IGC-TR")
        (field (name "MOUSER_PART_NUMBER") "696-SML-0606IGCTR")
      )
      (libsource (lib "eagle-import") (part "B38G3RGB"))
    )
    (comp (ref "LED92")
      (value "B38G3RGB")
      (footprint "eagle-import:B38G3RGB")
      (fields
        (field (name "ARROW_PART_NUMBER") "SML-LX0606IGC-TR")
        (field (name "MOUSER_PART_NUMBER") "696-SML-0606IGCTR")
      )
      (libsource (lib "eagle-import") (part "B38G3RGB"))
    )
    (comp (ref "LED93")
      (value "B38G3RGB")
      (footprint "eagle-import:B38G3RGB")
      (fields
        (field (name "ARROW_PART_NUMBER") "SML-LX0606IGC-TR")
        (field (name "MOUSER_PART_NUMBER") "696-SML-0606IGCTR")
      )
      (libsource (lib "eagle-import") (part "B38G3RGB"))
    )
    (comp (ref "LED94")
      (value "B38G3RGB")
      (footprint "eagle-import:B38G3RGB")
      (fields
        (field (name "ARROW_PART_NUMBER") "SML-LX0606IGC-TR")
        (field (name "MOUSER_PART_NUMBER") "696-SML-0606IGCTR")
      )
      (libsource (lib "eagle-import") (part "B38G3RGB"))
    )
    (comp (ref "LED95")
      (value "B38G3RGB")
      (footprint "eagle-import:B38G3RGB")
      (fields
        (field (name "ARROW_PART_NUMBER") "SML-LX0606IGC-TR")
        (field (name "MOUSER_PART_NUMBER") "696-SML-0606IGCTR")
      )
      (libsource (lib "eagle-import") (part "B38G3RGB"))
    )
    (comp (ref "LED96")
      (value "B38G3RGB")
      (footprint "eagle-import:B38G3RGB")
      (fields
        (field (name "ARROW_PART_NUMBER") "SML-LX0606IGC-TR")
        (field (name "MOUSER_PART_NUMBER") "696-SML-0606IGCTR")
      )
      (libsource (lib "eagle-import") (part "B38G3RGB"))
    )
    (comp (ref "LED97")
      (value "B38G3RGB")
      (footprint "eagle-import:B38G3RGB")
      (fields
        (field (name "ARROW_PART_NUMBER") "SML-LX0606IGC-TR")
        (field (name "MOUSER_PART_NUMBER") "696-SML-0606IGCTR")
      )
      (libsource (lib "eagle-import") (part "B38G3RGB"))
    )
    (comp (ref "LED98")
      (value "B38G3RGB")
      (footprint "eagle-import:B38G3RGB")
      (fields
        (field (name "ARROW_PART_NUMBER") "SML-LX0606IGC-TR")
        (field (name "MOUSER_PART_NUMBER") "696-SML-0606IGCTR")
      )
      (libsource (lib "eagle-import") (part "B38G3RGB"))
    )
    (comp (ref "LED99")
      (value "B38G3RGB")
      (footprint "eagle-import:B38G3RGB")
      (fields
        (field (name "ARROW_PART_NUMBER") "SML-LX0606IGC-TR")
        (field (name "MOUSER_PART_NUMBER") "696-SML-0606IGCTR")
      )
      (libsource (lib "eagle-import") (part "B38G3RGB"))
    )
    (comp (ref "LED100")
      (value "B38G3RGB")
      (footprint "eagle-import:B38G3RGB")
      (fields
        (field (name "ARROW_PART_NUMBER") "SML-LX0606IGC-TR")
        (field (name "MOUSER_PART_NUMBER") "696-SML-0606IGCTR")
      )
      (libsource (lib "eagle-import") (part "B38G3RGB"))
    )
    (comp (ref "LED101")
      (value "B38G3RGB")
      (footprint "eagle-import:B38G3RGB")
      (fields
        (field (name "ARROW_PART_NUMBER") "SML-LX0606IGC-TR")
        (field (name "MOUSER_PART_NUMBER") "696-SML-0606IGCTR")
      )
      (libsource (lib "eagle-import") (part "B38G3RGB"))
    )
    (comp (ref "LED102")
      (value "B38G3RGB")
      (footprint "eagle-import:B38G3RGB")
      (fields
        (field (name "ARROW_PART_NUMBER") "SML-LX0606IGC-TR")
        (field (name "MOUSER_PART_NUMBER") "696-SML-0606IGCTR")
      )
      (libsource (lib "eagle-import") (part "B38G3RGB"))
    )
    (comp (ref "LED103")
      (value "B38G3RGB")
      (footprint "eagle-import:B38G3RGB")
      (fields
        (field (name "ARROW_PART_NUMBER") "SML-LX0606IGC-TR")
        (field (name "MOUSER_PART_NUMBER") "696-SML-0606IGCTR")
      )
      (libsource (lib "eagle-import") (part "B38G3RGB"))
    )
    (comp (ref "LED104")
      (value "B38G3RGB")
      (footprint "eagle-import:B38G3RGB")
      (fields
        (field (name "ARROW_PART_NUMBER") "SML-LX0606IGC-TR")
        (field (name "MOUSER_PART_NUMBER") "696-SML-0606IGCTR")
      )
      (libsource (lib "eagle-import") (part "B38G3RGB"))
    )
    (comp (ref "LED105")
      (value "B38G3RGB")
      (footprint "eagle-import:B38G3RGB")
      (fields
        (field (name "ARROW_PART_NUMBER") "SML-LX0606IGC-TR")
        (field (name "MOUSER_PART_NUMBER") "696-SML-0606IGCTR")
      )
      (libsource (lib "eagle-import") (part "B38G3RGB"))
    )
    (comp (ref "LED106")
      (value "B38G3RGB")
      (footprint "eagle-import:B38G3RGB")
      (fields
        (field (name "ARROW_PART_NUMBER") "SML-LX0606IGC-TR")
        (field (name "MOUSER_PART_NUMBER") "696-SML-0606IGCTR")
      )
      (libsource (lib "eagle-import") (part "B38G3RGB"))
    )
    (comp (ref "LED107")
      (value "B38G3RGB")
      (footprint "eagle-import:B38G3RGB")
      (fields
        (field (name "ARROW_PART_NUMBER") "SML-LX0606IGC-TR")
        (field (name "MOUSER_PART_NUMBER") "696-SML-0606IGCTR")
      )
      (libsource (lib "eagle-import") (part "B38G3RGB"))
    )
    (comp (ref "LED108")
      (value "B38G3RGB")
      (footprint "eagle-import:B38G3RGB")
      (fields
        (field (name "ARROW_PART_NUMBER") "SML-LX0606IGC-TR")
        (field (name "MOUSER_PART_NUMBER") "696-SML-0606IGCTR")
      )
      (libsource (lib "eagle-import") (part "B38G3RGB"))
    )
    (comp (ref "LED109")
      (value "B38G3RGB")
      (footprint "eagle-import:B38G3RGB")
      (fields
        (field (name "ARROW_PART_NUMBER") "SML-LX0606IGC-TR")
        (field (name "MOUSER_PART_NUMBER") "696-SML-0606IGCTR")
      )
      (libsource (lib "eagle-import") (part "B38G3RGB"))
    )
    (comp (ref "LED110")
      (value "B38G3RGB")
      (footprint "eagle-import:B38G3RGB")
      (fields
        (field (name "ARROW_PART_NUMBER") "SML-LX0606IGC-TR")
        (field (name "MOUSER_PART_NUMBER") "696-SML-0606IGCTR")
      )
      (libsource (lib "eagle-import") (part "B38G3RGB"))
    )
    (comp (ref "LED111")
      (value "B38G3RGB")
      (footprint "eagle-import:B38G3RGB")
      (fields
        (field (name "ARROW_PART_NUMBER") "SML-LX0606IGC-TR")
        (field (name "MOUSER_PART_NUMBER") "696-SML-0606IGCTR")
      )
      (libsource (lib "eagle-import") (part "B38G3RGB"))
    )
    (comp (ref "LED112")
      (value "B38G3RGB")
      (footprint "eagle-import:B38G3RGB")
      (fields
        (field (name "ARROW_PART_NUMBER") "SML-LX0606IGC-TR")
        (field (name "MOUSER_PART_NUMBER") "696-SML-0606IGCTR")
      )
      (libsource (lib "eagle-import") (part "B38G3RGB"))
    )
    (comp (ref "LED113")
      (value "B38G3RGB")
      (footprint "eagle-import:B38G3RGB")
      (fields
        (field (name "ARROW_PART_NUMBER") "SML-LX0606IGC-TR")
        (field (name "MOUSER_PART_NUMBER") "696-SML-0606IGCTR")
      )
      (libsource (lib "eagle-import") (part "B38G3RGB"))
    )
    (comp (ref "LED114")
      (value "B38G3RGB")
      (footprint "eagle-import:B38G3RGB")
      (fields
        (field (name "ARROW_PART_NUMBER") "SML-LX0606IGC-TR")
        (field (name "MOUSER_PART_NUMBER") "696-SML-0606IGCTR")
      )
      (libsource (lib "eagle-import") (part "B38G3RGB"))
    )
    (comp (ref "LED115")
      (value "B38G3RGB")
      (footprint "eagle-import:B38G3RGB")
      (fields
        (field (name "ARROW_PART_NUMBER") "SML-LX0606IGC-TR")
        (field (name "MOUSER_PART_NUMBER") "696-SML-0606IGCTR")
      )
      (libsource (lib "eagle-import") (part "B38G3RGB"))
    )
    (comp (ref "LED116")
      (value "B38G3RGB")
      (footprint "eagle-import:B38G3RGB")
      (fields
        (field (name "ARROW_PART_NUMBER") "SML-LX0606IGC-TR")
        (field (name "MOUSER_PART_NUMBER") "696-SML-0606IGCTR")
      )
      (libsource (lib "eagle-import") (part "B38G3RGB"))
    )
    (comp (ref "LED117")
      (value "B38G3RGB")
      (footprint "eagle-import:B38G3RGB")
      (fields
        (field (name "ARROW_PART_NUMBER") "SML-LX0606IGC-TR")
        (field (name "MOUSER_PART_NUMBER") "696-SML-0606IGCTR")
      )
      (libsource (lib "eagle-import") (part "B38G3RGB"))
    )
    (comp (ref "LED118")
      (value "B38G3RGB")
      (footprint "eagle-import:B38G3RGB")
      (fields
        (field (name "ARROW_PART_NUMBER") "SML-LX0606IGC-TR")
        (field (name "MOUSER_PART_NUMBER") "696-SML-0606IGCTR")
      )
      (libsource (lib "eagle-import") (part "B38G3RGB"))
    )
    (comp (ref "LED119")
      (value "B38G3RGB")
      (footprint "eagle-import:B38G3RGB")
      (fields
        (field (name "ARROW_PART_NUMBER") "SML-LX0606IGC-TR")
        (field (name "MOUSER_PART_NUMBER") "696-SML-0606IGCTR")
      )
      (libsource (lib "eagle-import") (part "B38G3RGB"))
    )
    (comp (ref "LED120")
      (value "B38G3RGB")
      (footprint "eagle-import:B38G3RGB")
      (fields
        (field (name "ARROW_PART_NUMBER") "SML-LX0606IGC-TR")
        (field (name "MOUSER_PART_NUMBER") "696-SML-0606IGCTR")
      )
      (libsource (lib "eagle-import") (part "B38G3RGB"))
    )
    (comp (ref "SV1")
      (value "MA06-2")
      (footprint "eagle-import:MA06-2")
      (libsource (lib "eagle-import") (part "MA06-2"))
    )
  )
  (nets
    (net (code "1") (name "/3V3") (class "Default")
      (node (ref "LED1") (pin "3") (pinfunction "COM_3") (pintype "bidirectional"))
      (node (ref "LED10") (pin "3") (pinfunction "COM_3") (pintype "bidirectional"))
      (node (ref "LED100") (pin "3") (pinfunction "COM_3") (pintype "bidirectional"))
      (node (ref "LED101") (pin "3") (pinfunction "COM_3") (pintype "bidirectional"))
      (node (ref "LED102") (pin "3") (pinfunction "COM_3") (pintype "bidirectional"))
      (node (ref "LED103") (pin "3") (pinfunction "COM_3") (pintype "bidirectional"))
      (node (ref "LED104") (pin "3") (pinfunction "COM_3") (pintype "bidirectional"))
      (node (ref "LED105") (pin "3") (pinfunction "COM_3") (pintype "bidirectional"))
      (node (ref "LED106") (pin "3") (pinfunction "COM_3") (pintype "bidirectional"))
      (node (ref "LED107") (pin "3") (pinfunction "COM_3") (pintype "bidirectional"))
      (node (ref "LED108") (pin "3") (pinfunction "COM_3") (pintype "bidirectional"))
      (node (ref "LED109") (pin "3") (pinfunction "COM_3") (pintype "bidirectional"))
      (node (ref "LED11") (pin "3") (pinfunction "COM_3") (pintype "bidirectional"))
      (node (ref "LED110") (pin "3") (pinfunction "COM_3") (pintype "bidirectional"))
      (node (ref "LED111") (pin "3") (pinfunction "COM_3") (pintype "bidirectional"))
      (node (ref "LED112") (pin "3") (pinfunction "COM_3") (pintype "bidirectional"))
      (node (ref "LED113") (pin "3") (pinfunction "COM_3") (pintype "bidirectional"))
      (node (ref "LED114") (pin "3") (pinfunction "COM_3") (pintype "bidirectional"))
      (node (ref "LED115") (pin "3") (pinfunction "COM_3") (pintype "bidirectional"))
      (node (ref "LED116") (pin "3") (pinfunction "COM_3") (pintype "bidirectional"))
      (node (ref "LED117") (pin "3") (pinfunction "COM_3") (pintype "bidirectional"))
      (node (ref "LED118") (pin "3") (pinfunction "COM_3") (pintype "bidirectional"))
      (node (ref "LED119") (pin "3") (pinfunction "COM_3") (pintype "bidirectional"))
      (node (ref "LED12") (pin "3") (pinfunction "COM_3") (pintype "bidirectional"))
      (node (ref "LED120") (pin "3") (pinfunction "COM_3") (pintype "bidirectional"))
      (node (ref "LED13") (pin "3") (pinfunction "COM_3") (pintype "bidirectional"))
      (node (ref "LED14") (pin "3") (pinfunction "COM_3") (pintype "bidirectional"))
      (node (ref "LED15") (pin "3") (pinfunction "COM_3") (pintype "bidirectional"))
      (node (ref "LED16") (pin "3") (pinfunction "COM_3") (pintype "bidirectional"))
      (node (ref "LED17") (pin "3") (pinfunction "COM_3") (pintype "bidirectional"))
      (node (ref "LED18") (pin "3") (pinfunction "COM_3") (pintype "bidirectional"))
      (node (ref "LED19") (pin "3") (pinfunction "COM_3") (pintype "bidirectional"))
      (node (ref "LED2") (pin "3") (pinfunction "COM_3") (pintype "bidirectional"))
      (node (ref "LED20") (pin "3") (pinfunction "COM_3") (pintype "bidirectional"))
      (node (ref "LED21") (pin "3") (pinfunction "COM_3") (pintype "bidirectional"))
      (node (ref "LED22") (pin "3") (pinfunction "COM_3") (pintype "bidirectional"))
      (node (ref "LED23") (pin "3") (pinfunction "COM_3") (pintype "bidirectional"))
      (node (ref "LED24") (pin "3") (pinfunction "COM_3") (pintype "bidirectional"))
      (node (ref "LED25") (pin "3") (pinfunction "COM_3") (pintype "bidirectional"))
      (node (ref "LED26") (pin "3") (pinfunction "COM_3") (pintype "bidirectional"))
      (node (ref "LED27") (pin "3") (pinfunction "COM_3") (pintype "bidirectional"))
      (node (ref "LED28") (pin "3") (pinfunction "COM_3") (pintype "bidirectional"))
      (node (ref "LED29") (pin "3") (pinfunction "COM_3") (pintype "bidirectional"))
      (node (ref "LED3") (pin "3") (pinfunction "COM_3") (pintype "bidirectional"))
      (node (ref "LED30") (pin "3") (pinfunction "COM_3") (pintype "bidirectional"))
      (node (ref "LED31") (pin "3") (pinfunction "COM_3") (pintype "bidirectional"))
      (node (ref "LED32") (pin "3") (pinfunction "COM_3") (pintype "bidirectional"))
      (node (ref "LED33") (pin "3") (pinfunction "COM_3") (pintype "bidirectional"))
      (node (ref "LED34") (pin "3") (pinfunction "COM_3") (pintype "bidirectional"))
      (node (ref "LED35") (pin "3") (pinfunction "COM_3") (pintype "bidirectional"))
      (node (ref "LED36") (pin "3") (pinfunction "COM_3") (pintype "bidirectional"))
      (node (ref "LED37") (pin "3") (pinfunction "COM_3") (pintype "bidirectional"))
      (node (ref "LED38") (pin "3") (pinfunction "COM_3") (pintype "bidirectional"))
      (node (ref "LED39") (pin "3") (pinfunction "COM_3") (pintype "bidirectional"))
      (node (ref "LED4") (pin "3") (pinfunction "COM_3") (pintype "bidirectional"))
      (node (ref "LED40") (pin "3") (pinfunction "COM_3") (pintype "bidirectional"))
      (node (ref "LED41") (pin "3") (pinfunction "COM_3") (pintype "bidirectional"))
      (node (ref "LED42") (pin "3") (pinfunction "COM_3") (pintype "bidirectional"))
      (node (ref "LED43") (pin "3") (pinfunction "COM_3") (pintype "bidirectional"))
      (node (ref "LED44") (pin "3") (pinfunction "COM_3") (pintype "bidirectional"))
      (node (ref "LED45") (pin "3") (pinfunction "COM_3") (pintype "bidirectional"))
      (node (ref "LED46") (pin "3") (pinfunction "COM_3") (pintype "bidirectional"))
      (node (ref "LED47") (pin "3") (pinfunction "COM_3") (pintype "bidirectional"))
      (node (ref "LED48") (pin "3") (pinfunction "COM_3") (pintype "bidirectional"))
      (node (ref "LED49") (pin "3") (pinfunction "COM_3") (pintype "bidirectional"))
      (node (ref "LED5") (pin "3") (pinfunction "COM_3") (pintype "bidirectional"))
      (node (ref "LED50") (pin "3") (pinfunction "COM_3") (pintype "bidirectional"))
      (node (ref "LED51") (pin "3") (pinfunction "COM_3") (pintype "bidirectional"))
      (node (ref "LED52") (pin "3") (pinfunction "COM_3") (pintype "bidirectional"))
      (node (ref "LED53") (pin "3") (pinfunction "COM_3") (pintype "bidirectional"))
      (node (ref "LED54") (pin "3") (pinfunction "COM_3") (pintype "bidirectional"))
      (node (ref "LED55") (pin "3") (pinfunction "COM_3") (pintype "bidirectional"))
      (node (ref "LED56") (pin "3") (pinfunction "COM_3") (pintype "bidirectional"))
      (node (ref "LED57") (pin "3") (pinfunction "COM_3") (pintype "bidirectional"))
      (node (ref "LED58") (pin "3") (pinfunction "COM_3") (pintype "bidirectional"))
      (node (ref "LED59") (pin "3") (pinfunction "COM_3") (pintype "bidirectional"))
      (node (ref "LED6") (pin "3") (pinfunction "COM_3") (pintype "bidirectional"))
      (node (ref "LED60") (pin "3") (pinfunction "COM_3") (pintype "bidirectional"))
      (node (ref "LED61") (pin "3") (pinfunction "COM_3") (pintype "bidirectional"))
      (node (ref "LED62") (pin "3") (pinfunction "COM_3") (pintype "bidirectional"))
      (node (ref "LED63") (pin "3") (pinfunction "COM_3") (pintype "bidirectional"))
      (node (ref "LED64") (pin "3") (pinfunction "COM_3") (pintype "bidirectional"))
      (node (ref "LED65") (pin "3") (pinfunction "COM_3") (pintype "bidirectional"))
      (node (ref "LED66") (pin "3") (pinfunction "COM_3") (pintype "bidirectional"))
      (node (ref "LED67") (pin "3") (pinfunction "COM_3") (pintype "bidirectional"))
      (node (ref "LED68") (pin "3") (pinfunction "COM_3") (pintype "bidirectional"))
      (node (ref "LED69") (pin "3") (pinfunction "COM_3") (pintype "bidirectional"))
      (node (ref "LED7") (pin "3") (pinfunction "COM_3") (pintype "bidirectional"))
      (node (ref "LED70") (pin "3") (pinfunction "COM_3") (pintype "bidirectional"))
      (node (ref "LED71") (pin "3") (pinfunction "COM_3") (pintype "bidirectional"))
      (node (ref "LED72") (pin "3") (pinfunction "COM_3") (pintype "bidirectional"))
      (node (ref "LED73") (pin "3") (pinfunction "COM_3") (pintype "bidirectional"))
      (node (ref "LED74") (pin "3") (pinfunction "COM_3") (pintype "bidirectional"))
      (node (ref "LED75") (pin "3") (pinfunction "COM_3") (pintype "bidirectional"))
      (node (ref "LED76") (pin "3") (pinfunction "COM_3") (pintype "bidirectional"))
      (node (ref "LED77") (pin "3") (pinfunction "COM_3") (pintype "bidirectional"))
      (node (ref "LED78") (pin "3") (pinfunction "COM_3") (pintype "bidirectional"))
      (node (ref "LED79") (pin "3") (pinfunction "COM_3") (pintype "bidirectional"))
      (node (ref "LED8") (pin "3") (pinfunction "COM_3") (pintype "bidirectional"))
      (node (ref "LED80") (pin "3") (pinfunction "COM_3") (pintype "bidirectional"))
      (node (ref "LED81") (pin "3") (pinfunction "COM_3") (pintype "bidirectional"))
      (node (ref "LED82") (pin "3") (pinfunction "COM_3") (pintype "bidirectional"))
      (node (ref "LED83") (pin "3") (pinfunction "COM_3") (pintype "bidirectional"))
      (node (ref "LED84") (pin "3") (pinfunction "COM_3") (pintype "bidirectional"))
      (node (ref "LED85") (pin "3") (pinfunction "COM_3") (pintype "bidirectional"))
      (node (ref "LED86") (pin "3") (pinfunction "COM_3") (pintype "bidirectional"))
      (node (ref "LED87") (pin "3") (pinfunction "COM_3") (pintype "bidirectional"))
      (node (ref "LED88") (pin "3") (pinfunction "COM_3") (pintype "bidirectional"))
      (node (ref "LED89") (pin "3") (pinfunction "COM_3") (pintype "bidirectional"))
      (node (ref "LED9") (pin "3") (pinfunction "COM_3") (pintype "bidirectional"))
      (node (ref "LED90") (pin "3") (pinfunction "COM_3") (pintype "bidirectional"))
      (node (ref "LED91") (pin "3") (pinfunction "COM_3") (pintype "bidirectional"))
      (node (ref "LED92") (pin "3") (pinfunction "COM_3") (pintype "bidirectional"))
      (node (ref "LED93") (pin "3") (pinfunction "COM_3") (pintype "bidirectional"))
      (node (ref "LED94") (pin "3") (pinfunction "COM_3") (pintype "bidirectional"))
      (node (ref "LED95") (pin "3") (pinfunction "COM_3") (pintype "bidirectional"))
      (node (ref "LED96") (pin "3") (pinfunction "COM_3") (pintype "bidirectional"))
      (node (ref "LED97") (pin "3") (pinfunction "COM_3") (pintype "bidirectional"))
      (node (ref "LED98") (pin "3") (pinfunction "COM_3") (pintype "bidirectional"))
      (node (ref "LED99") (pin "3") (pinfunction "COM_3") (pintype "bidirectional"))
      (node (ref "SV1") (pin "6") (pinfunction "6_6") (pintype "passive"))
      (node (ref "SV1") (pin "8") (pinfunction "8_8") (pintype "passive"))
    )
    (net (code "2") (name "/GND") (class "Default")
      (node (ref "C1") (pin "2") (pinfunction "2_2") (pintype "passive"))
      (node (ref "C1B") (pin "2") (pinfunction "2_2") (pintype "passive"))
      (node (ref "C2") (pin "2") (pinfunction "2_2") (pintype "passive"))
      (node (ref "C28") (pin "2") (pinfunction "2_2") (pintype "passive"))
      (node (ref "C29") (pin "2") (pinfunction "2_2") (pintype "passive"))
      (node (ref "C2B") (pin "2") (pinfunction "2_2") (pintype "passive"))
      (node (ref "C3") (pin "2") (pinfunction "2_2") (pintype "passive"))
      (node (ref "C30") (pin "2") (pinfunction "2_2") (pintype "passive"))
      (node (ref "C31") (pin "2") (pinfunction "2_2") (pintype "passive"))
      (node (ref "C32") (pin "2") (pinfunction "2_2") (pintype "passive"))
      (node (ref "C33") (pin "2") (pinfunction "2_2") (pintype "passive"))
      (node (ref "C3B") (pin "2") (pinfunction "2_2") (pintype "passive"))
      (node (ref "C4") (pin "2") (pinfunction "2_2") (pintype "passive"))
      (node (ref "C4B") (pin "2") (pinfunction "2_2") (pintype "passive"))
      (node (ref "C5") (pin "2") (pinfunction "2_2") (pintype "passive"))
      (node (ref "C5B") (pin "2") (pinfunction "2_2") (pintype "passive"))
      (node (ref "C6") (pin "2") (pinfunction "2_2") (pintype "passive"))
      (node (ref "C6B") (pin "2") (pinfunction "2_2") (pintype "passive"))
      (node (ref "C7") (pin "2") (pinfunction "2_2") (pintype "passive"))
      (node (ref "C7B") (pin "2") (pinfunction "2_2") (pintype "passive"))
      (node (ref "C8") (pin "2") (pinfunction "2_2") (pintype "passive"))
      (node (ref "C8B") (pin "2") (pinfunction "2_2") (pintype "passive"))
      (node (ref "IC1") (pin "29") (pinfunction "GND_1_29") (pintype "bidirectional"))
      (node (ref "IC1") (pin "56") (pinfunction "GND_2_56") (pintype "bidirectional"))
      (node (ref "IC1") (pin "57") (pinfunction "THERMALPAD_57") (pintype "bidirectional"))
      (node (ref "IC10") (pin "3") (pinfunction "GND_3") (pintype "bidirectional"))
      (node (ref "IC11") (pin "3") (pinfunction "GND_3") (pintype "bidirectional"))
      (node (ref "IC2") (pin "29") (pinfunction "GND_1_29") (pintype "bidirectional"))
      (node (ref "IC2") (pin "56") (pinfunction "GND_2_56") (pintype "bidirectional"))
      (node (ref "IC2") (pin "57") (pinfunction "THERMALPAD_57") (pintype "bidirectional"))
      (node (ref "IC3") (pin "29") (pinfunction "GND_1_29") (pintype "bidirectional"))
      (node (ref "IC3") (pin "56") (pinfunction "GND_2_56") (pintype "bidirectional"))
      (node (ref "IC3") (pin "57") (pinfunction "THERMALPAD_57") (pintype "bidirectional"))
      (node (ref "IC4") (pin "29") (pinfunction "GND_1_29") (pintype "bidirectional"))
      (node (ref "IC4") (pin "56") (pinfunction "GND_2_56") (pintype "bidirectional"))
      (node (ref "IC4") (pin "57") (pinfunction "THERMALPAD_57") (pintype "bidirectional"))
      (node (ref "IC5") (pin "29") (pinfunction "GND_1_29") (pintype "bidirectional"))
      (node (ref "IC5") (pin "56") (pinfunction "GND_2_56") (pintype "bidirectional"))
      (node (ref "IC5") (pin "57") (pinfunction "THERMALPAD_57") (pintype "bidirectional"))
      (node (ref "IC6") (pin "29") (pinfunction "GND_1_29") (pintype "bidirectional"))
      (node (ref "IC6") (pin "56") (pinfunction "GND_2_56") (pintype "bidirectional"))
      (node (ref "IC6") (pin "57") (pinfunction "THERMALPAD_57") (pintype "bidirectional"))
      (node (ref "IC7") (pin "29") (pinfunction "GND_1_29") (pintype "bidirectional"))
      (node (ref "IC7") (pin "56") (pinfunction "GND_2_56") (pintype "bidirectional"))
      (node (ref "IC7") (pin "57") (pinfunction "THERMALPAD_57") (pintype "bidirectional"))
      (node (ref "IC8") (pin "29") (pinfunction "GND_1_29") (pintype "bidirectional"))
      (node (ref "IC8") (pin "56") (pinfunction "GND_2_56") (pintype "bidirectional"))
      (node (ref "IC8") (pin "57") (pinfunction "THERMALPAD_57") (pintype "bidirectional"))
      (node (ref "IC9") (pin "3") (pinfunction "GND_3") (pintype "bidirectional"))
      (node (ref "SV1") (pin "2") (pinfunction "2_2") (pintype "passive"))
      (node (ref "SV1") (pin "4") (pinfunction "4_4") (pintype "passive"))
    )
    (net (code "3") (name "/N$352") (class "Default")
      (node (ref "IC8") (pin "53") (pinfunction "OUTB8_53") (pintype "bidirectional"))
    )
    (net (code "4") (name "/N$353") (class "Default")
      (node (ref "IC8") (pin "52") (pinfunction "OUTR8_52") (pintype "bidirectional"))
    )
    (net (code "5") (name "/N$354") (class "Default")
      (node (ref "IC8") (pin "51") (pinfunction "OUTG8_51") (pintype "bidirectional"))
    )
    (net (code "6") (name "/N$355") (class "Default")
      (node (ref "IC8") (pin "50") (pinfunction "OUTB12_50") (pintype "bidirectional"))
    )
    (net (code "7") (name "/N$356") (class "Default")
      (node (ref "IC8") (pin "49") (pinfunction "OUTR12_49") (pintype "bidirectional"))
    )
    (net (code "8") (name "/N$357") (class "Default")
      (node (ref "IC8") (pin "48") (pinfunction "OUTG12_48") (pintype "bidirectional"))
    )
    (net (code "9") (name "/N$358") (class "Default")
      (node (ref "IC8") (pin "47") (pinfunction "OUTB9_47") (pintype "bidirectional"))
    )
    (net (code "10") (name "/N$359") (class "Default")
      (node (ref "IC8") (pin "46") (pinfunction "OUTR9_46") (pintype "bidirectional"))
    )
    (net (code "11") (name "/N$360") (class "Default")
      (node (ref "IC8") (pin "45") (pinfunction "OUTG9_45") (pintype "bidirectional"))
    )
    (net (code "12") (name "/N$361") (class "Default")
      (node (ref "IC8") (pin "44") (pinfunction "OUTB13_44") (pintype "bidirectional"))
    )
    (net (code "13") (name "/N$362") (class "Default")
      (node (ref "IC8") (pin "43") (pinfunction "OUTR13_43") (pintype "bidirectional"))
    )
    (net (code "14") (name "/N$363") (class "Default")
      (node (ref "IC8") (pin "42") (pinfunction "OUTG13_42") (pintype "bidirectional"))
    )
    (net (code "15") (name "/N$IC8_PIN4") (class "Default")
      (node (ref "IC8") (pin "4") (pinfunction "OUTB4_4") (pintype "bidirectional"))
    )
    (net (code "16") (name "/N$IC8_PIN5") (class "Default")
      (node (ref "IC8") (pin "5") (pinfunction "OUTR4_5") (pintype "bidirectional"))
    )
    (net (code "17") (name "/N$IC8_PIN6") (class "Default")
      (node (ref "IC8") (pin "6") (pinfunction "OUTG4_6") (pintype "bidirectional"))
    )
    (net (code "18") (name "/N$IC8_PIN7") (class "Default")
      (node (ref "IC8") (pin "7") (pinfunction "OUTB0_7") (pintype "bidirectional"))
    )
    (net (code "19") (name "/N$IC8_PIN8") (class "Default")
      (node (ref "IC8") (pin "8") (pinfunction "OUTR0_8") (pintype "bidirectional"))
    )
    (net (code "20") (name "/N$IC8_PIN9") (class "Default")
      (node (ref "IC8") (pin "9") (pinfunction "OUTG0_9") (pintype "bidirectional"))
    )
    (net (code "21") (name "/N$IC8_PIN10") (class "Default")
      (node (ref "IC8") (pin "10") (pinfunction "OUTB5_10") (pintype "bidirectional"))
    )
    (net (code "22") (name "/N$IC8_PIN11") (class "Default")
      (node (ref "IC8") (pin "11") (pinfunction "OUTR5_11") (pintype "bidirectional"))
    )
    (net (code "23") (name "/N$IC8_PIN12") (class "Default")
      (node (ref "IC8") (pin "12") (pinfunction "OUTG5_12") (pintype "bidirectional"))
    )
    (net (code "24") (name "/N$IC8_PIN13") (class "Default")
      (node (ref "IC8") (pin "13") (pinfunction "OUTB1_13") (pintype "bidirectional"))
    )
    (net (code "25") (name "/N$IC8_PIN14") (class "Default")
      (node (ref "IC8") (pin "14") (pinfunction "OUTR1_14") (pintype "bidirectional"))
    )
    (net (code "26") (name "/N$IC8_PIN15") (class "Default")
      (node (ref "IC8") (pin "15") (pinfunction "OUTG1_15") (pintype "bidirectional"))
    )
    (net (code "27") (name "/N$LEDB1") (class "Default")
      (node (ref "IC1") (pin "25") (pinfunction "OUTB7_25") (pintype "bidirectional"))
      (node (ref "LED1") (pin "2") (pinfunction "BLUE_2") (pintype "bidirectional"))
    )
    (net (code "28") (name "/N$LEDB2") (class "Default")
      (node (ref "IC1") (pin "22") (pinfunction "OUTB3_22") (pintype "bidirectional"))
      (node (ref "LED2") (pin "2") (pinfunction "BLUE_2") (pintype "bidirectional"))
    )
    (net (code "29") (name "/N$LEDB3") (class "Default")
      (node (ref "IC1") (pin "32") (pinfunction "OUTB11_32") (pintype "bidirectional"))
      (node (ref "LED3") (pin "2") (pinfunction "BLUE_2") (pintype "bidirectional"))
    )
    (net (code "30") (name "/N$LEDB4") (class "Default")
      (node (ref "IC1") (pin "35") (pinfunction "OUTB15_35") (pintype "bidirectional"))
      (node (ref "LED4") (pin "2") (pinfunction "BLUE_2") (pintype "bidirectional"))
    )
    (net (code "31") (name "/N$LEDB5") (class "Default")
      (node (ref "IC1") (pin "19") (pinfunction "OUTB6_19") (pintype "bidirectional"))
      (node (ref "LED5") (pin "2") (pinfunction "BLUE_2") (pintype "bidirectional"))
    )
    (net (code "32") (name "/N$LEDB6") (class "Default")
      (node (ref "IC1") (pin "16") (pinfunction "OUTB2_16") (pintype "bidirectional"))
      (node (ref "LED6") (pin "2") (pinfunction "BLUE_2") (pintype "bidirectional"))
    )
    (net (code "33") (name "/N$LEDB7") (class "Default")
      (node (ref "IC1") (pin "38") (pinfunction "OUTB10_38") (pintype "bidirectional"))
      (node (ref "LED7") (pin "2") (pinfunction "BLUE_2") (pintype "bidirectional"))
    )
    (net (code "34") (name "/N$LEDB8") (class "Default")
      (node (ref "IC1") (pin "41") (pinfunction "OUTB14_41") (pintype "bidirectional"))
      (node (ref "LED8") (pin "2") (pinfunction "BLUE_2") (pintype "bidirectional"))
    )
    (net (code "35") (name "/N$LEDB9") (class "Default")
      (node (ref "IC1") (pin "13") (pinfunction "OUTB1_13") (pintype "bidirectional"))
      (node (ref "LED9") (pin "2") (pinfunction "BLUE_2") (pintype "bidirectional"))
    )
    (net (code "36") (name "/N$LEDB10") (class "Default")
      (node (ref "IC1") (pin "10") (pinfunction "OUTB5_10") (pintype "bidirectional"))
      (node (ref "LED10") (pin "2") (pinfunction "BLUE_2") (pintype "bidirectional"))
    )
    (net (code "37") (name "/N$LEDB11") (class "Default")
      (node (ref "IC1") (pin "44") (pinfunction "OUTB13_44") (pintype "bidirectional"))
      (node (ref "LED11") (pin "2") (pinfunction "BLUE_2") (pintype "bidirectional"))
    )
    (net (code "38") (name "/N$LEDB12") (class "Default")
      (node (ref "IC1") (pin "47") (pinfunction "OUTB9_47") (pintype "bidirectional"))
      (node (ref "LED12") (pin "2") (pinfunction "BLUE_2") (pintype "bidirectional"))
    )
    (net (code "39") (name "/N$LEDB13") (class "Default")
      (node (ref "IC1") (pin "4") (pinfunction "OUTB4_4") (pintype "bidirectional"))
      (node (ref "LED13") (pin "2") (pinfunction "BLUE_2") (pintype "bidirectional"))
    )
    (net (code "40") (name "/N$LEDB14") (class "Default")
      (node (ref "IC1") (pin "7") (pinfunction "OUTB0_7") (pintype "bidirectional"))
      (node (ref "LED14") (pin "2") (pinfunction "BLUE_2") (pintype "bidirectional"))
    )
    (net (code "41") (name "/N$LEDB15") (class "Default")
      (node (ref "IC1") (pin "50") (pinfunction "OUTB12_50") (pintype "bidirectional"))
      (node (ref "LED15") (pin "2") (pinfunction "BLUE_2") (pintype "bidirectional"))
    )
    (net (code "42") (name "/N$LEDB16") (class "Default")
      (node (ref "IC1") (pin "53") (pinfunction "OUTB8_53") (pintype "bidirectional"))
      (node (ref "LED16") (pin "2") (pinfunction "BLUE_2") (pintype "bidirectional"))
    )
    (net (code "43") (name "/N$LEDB17") (class "Default")
      (node (ref "IC2") (pin "25") (pinfunction "OUTB7_25") (pintype "bidirectional"))
      (node (ref "LED17") (pin "2") (pinfunction "BLUE_2") (pintype "bidirectional"))
    )
    (net (code "44") (name "/N$LEDB18") (class "Default")
      (node (ref "IC2") (pin "22") (pinfunction "OUTB3_22") (pintype "bidirectional"))
      (node (ref "LED18") (pin "2") (pinfunction "BLUE_2") (pintype "bidirectional"))
    )
    (net (code "45") (name "/N$LEDB19") (class "Default")
      (node (ref "IC2") (pin "32") (pinfunction "OUTB11_32") (pintype "bidirectional"))
      (node (ref "LED19") (pin "2") (pinfunction "BLUE_2") (pintype "bidirectional"))
    )
    (net (code "46") (name "/N$LEDB20") (class "Default")
      (node (ref "IC2") (pin "35") (pinfunction "OUTB15_35") (pintype "bidirectional"))
      (node (ref "LED20") (pin "2") (pinfunction "BLUE_2") (pintype "bidirectional"))
    )
    (net (code "47") (name "/N$LEDB21") (class "Default")
      (node (ref "IC2") (pin "19") (pinfunction "OUTB6_19") (pintype "bidirectional"))
      (node (ref "LED21") (pin "2") (pinfunction "BLUE_2") (pintype "bidirectional"))
    )
    (net (code "48") (name "/N$LEDB22") (class "Default")
      (node (ref "IC2") (pin "16") (pinfunction "OUTB2_16") (pintype "bidirectional"))
      (node (ref "LED22") (pin "2") (pinfunction "BLUE_2") (pintype "bidirectional"))
    )
    (net (code "49") (name "/N$LEDB23") (class "Default")
      (node (ref "IC2") (pin "38") (pinfunction "OUTB10_38") (pintype "bidirectional"))
      (node (ref "LED23") (pin "2") (pinfunction "BLUE_2") (pintype "bidirectional"))
    )
    (net (code "50") (name "/N$LEDB24") (class "Default")
      (node (ref "IC2") (pin "41") (pinfunction "OUTB14_41") (pintype "bidirectional"))
      (node (ref "LED24") (pin "2") (pinfunction "BLUE_2") (pintype "bidirectional"))
    )
    (net (code "51") (name "/N$LEDB25") (class "Default")
      (node (ref "IC2") (pin "13") (pinfunction "OUTB1_13") (pintype "bidirectional"))
      (node (ref "LED25") (pin "2") (pinfunction "BLUE_2") (pintype "bidirectional"))
    )
    (net (code "52") (name "/N$LEDB26") (class "Default")
      (node (ref "IC2") (pin "10") (pinfunction "OUTB5_10") (pintype "bidirectional"))
      (node (ref "LED26") (pin "2") (pinfunction "BLUE_2") (pintype "bidirectional"))
    )
    (net (code "53") (name "/N$LEDB27") (class "Default")
      (node (ref "IC2") (pin "44") (pinfunction "OUTB13_44") (pintype "bidirectional"))
      (node (ref "LED27") (pin "2") (pinfunction "BLUE_2") (pintype "bidirectional"))
    )
    (net (code "54") (name "/N$LEDB28") (class "Default")
      (node (ref "IC2") (pin "47") (pinfunction "OUTB9_47") (pintype "bidirectional"))
      (node (ref "LED28") (pin "2") (pinfunction "BLUE_2") (pintype "bidirectional"))
    )
    (net (code "55") (name "/N$LEDB29") (class "Default")
      (node (ref "IC2") (pin "4") (pinfunction "OUTB4_4") (pintype "bidirectional"))
      (node (ref "LED29") (pin "2") (pinfunction "BLUE_2") (pintype "bidirectional"))
    )
    (net (code "56") (name "/N$LEDB30") (class "Default")
      (node (ref "IC2") (pin "7") (pinfunction "OUTB0_7") (pintype "bidirectional"))
      (node (ref "LED30") (pin "2") (pinfunction "BLUE_2") (pintype "bidirectional"))
    )
    (net (code "57") (name "/N$LEDB31") (class "Default")
      (node (ref "IC2") (pin "50") (pinfunction "OUTB12_50") (pintype "bidirectional"))
      (node (ref "LED31") (pin "2") (pinfunction "BLUE_2") (pintype "bidirectional"))
    )
    (net (code "58") (name "/N$LEDB32") (class "Default")
      (node (ref "IC2") (pin "53") (pinfunction "OUTB8_53") (pintype "bidirectional"))
      (node (ref "LED32") (pin "2") (pinfunction "BLUE_2") (pintype "bidirectional"))
    )
    (net (code "59") (name "/N$LEDB33") (class "Default")
      (node (ref "IC3") (pin "25") (pinfunction "OUTB7_25") (pintype "bidirectional"))
      (node (ref "LED33") (pin "2") (pinfunction "BLUE_2") (pintype "bidirectional"))
    )
    (net (code "60") (name "/N$LEDB34") (class "Default")
      (node (ref "IC3") (pin "22") (pinfunction "OUTB3_22") (pintype "bidirectional"))
      (node (ref "LED34") (pin "2") (pinfunction "BLUE_2") (pintype "bidirectional"))
    )
    (net (code "61") (name "/N$LEDB35") (class "Default")
      (node (ref "IC3") (pin "32") (pinfunction "OUTB11_32") (pintype "bidirectional"))
      (node (ref "LED35") (pin "2") (pinfunction "BLUE_2") (pintype "bidirectional"))
    )
    (net (code "62") (name "/N$LEDB36") (class "Default")
      (node (ref "IC3") (pin "35") (pinfunction "OUTB15_35") (pintype "bidirectional"))
      (node (ref "LED36") (pin "2") (pinfunction "BLUE_2") (pintype "bidirectional"))
    )
    (net (code "63") (name "/N$LEDB37") (class "Default")
      (node (ref "IC3") (pin "19") (pinfunction "OUTB6_19") (pintype "bidirectional"))
      (node (ref "LED37") (pin "2") (pinfunction "BLUE_2") (pintype "bidirectional"))
    )
    (net (code "64") (name "/N$LEDB38") (class "Default")
      (node (ref "IC3") (pin "16") (pinfunction "OUTB2_16") (pintype "bidirectional"))
      (node (ref "LED38") (pin "2") (pinfunction "BLUE_2") (pintype "bidirectional"))
    )
    (net (code "65") (name "/N$LEDB39") (class "Default")
      (node (ref "IC3") (pin "38") (pinfunction "OUTB10_38") (pintype "bidirectional"))
      (node (ref "LED39") (pin "2") (pinfunction "BLUE_2") (pintype "bidirectional"))
    )
    (net (code "66") (name "/N$LEDB40") (class "Default")
      (node (ref "IC3") (pin "41") (pinfunction "OUTB14_41") (pintype "bidirectional"))
      (node (ref "LED40") (pin "2") (pinfunction "BLUE_2") (pintype "bidirectional"))
    )
    (net (code "67") (name "/N$LEDB41") (class "Default")
      (node (ref "IC3") (pin "13") (pinfunction "OUTB1_13") (pintype "bidirectional"))
      (node (ref "LED41") (pin "2") (pinfunction "BLUE_2") (pintype "bidirectional"))
    )
    (net (code "68") (name "/N$LEDB42") (class "Default")
      (node (ref "IC3") (pin "10") (pinfunction "OUTB5_10") (pintype "bidirectional"))
      (node (ref "LED42") (pin "2") (pinfunction "BLUE_2") (pintype "bidirectional"))
    )
    (net (code "69") (name "/N$LEDB43") (class "Default")
      (node (ref "IC3") (pin "44") (pinfunction "OUTB13_44") (pintype "bidirectional"))
      (node (ref "LED43") (pin "2") (pinfunction "BLUE_2") (pintype "bidirectional"))
    )
    (net (code "70") (name "/N$LEDB44") (class "Default")
      (node (ref "IC3") (pin "47") (pinfunction "OUTB9_47") (pintype "bidirectional"))
      (node (ref "LED44") (pin "2") (pinfunction "BLUE_2") (pintype "bidirectional"))
    )
    (net (code "71") (name "/N$LEDB45") (class "Default")
      (node (ref "IC3") (pin "4") (pinfunction "OUTB4_4") (pintype "bidirectional"))
      (node (ref "LED45") (pin "2") (pinfunction "BLUE_2") (pintype "bidirectional"))
    )
    (net (code "72") (name "/N$LEDB46") (class "Default")
      (node (ref "IC3") (pin "7") (pinfunction "OUTB0_7") (pintype "bidirectional"))
      (node (ref "LED46") (pin "2") (pinfunction "BLUE_2") (pintype "bidirectional"))
    )
    (net (code "73") (name "/N$LEDB47") (class "Default")
      (node (ref "IC3") (pin "50") (pinfunction "OUTB12_50") (pintype "bidirectional"))
      (node (ref "LED47") (pin "2") (pinfunction "BLUE_2") (pintype "bidirectional"))
    )
    (net (code "74") (name "/N$LEDB48") (class "Default")
      (node (ref "IC3") (pin "53") (pinfunction "OUTB8_53") (pintype "bidirectional"))
      (node (ref "LED48") (pin "2") (pinfunction "BLUE_2") (pintype "bidirectional"))
    )
    (net (code "75") (name "/N$LEDB49") (class "Default")
      (node (ref "IC4") (pin "25") (pinfunction "OUTB7_25") (pintype "bidirectional"))
      (node (ref "LED49") (pin "2") (pinfunction "BLUE_2") (pintype "bidirectional"))
    )
    (net (code "76") (name "/N$LEDB50") (class "Default")
      (node (ref "IC4") (pin "22") (pinfunction "OUTB3_22") (pintype "bidirectional"))
      (node (ref "LED50") (pin "2") (pinfunction "BLUE_2") (pintype "bidirectional"))
    )
    (net (code "77") (name "/N$LEDB51") (class "Default")
      (node (ref "IC4") (pin "32") (pinfunction "OUTB11_32") (pintype "bidirectional"))
      (node (ref "LED51") (pin "2") (pinfunction "BLUE_2") (pintype "bidirectional"))
    )
    (net (code "78") (name "/N$LEDB52") (class "Default")
      (node (ref "IC4") (pin "35") (pinfunction "OUTB15_35") (pintype "bidirectional"))
      (node (ref "LED52") (pin "2") (pinfunction "BLUE_2") (pintype "bidirectional"))
    )
    (net (code "79") (name "/N$LEDB53") (class "Default")
      (node (ref "IC4") (pin "19") (pinfunction "OUTB6_19") (pintype "bidirectional"))
      (node (ref "LED53") (pin "2") (pinfunction "BLUE_2") (pintype "bidirectional"))
    )
    (net (code "80") (name "/N$LEDB54") (class "Default")
      (node (ref "IC4") (pin "16") (pinfunction "OUTB2_16") (pintype "bidirectional"))
      (node (ref "LED54") (pin "2") (pinfunction "BLUE_2") (pintype "bidirectional"))
    )
    (net (code "81") (name "/N$LEDB55") (class "Default")
      (node (ref "IC4") (pin "38") (pinfunction "OUTB10_38") (pintype "bidirectional"))
      (node (ref "LED55") (pin "2") (pinfunction "BLUE_2") (pintype "bidirectional"))
    )
    (net (code "82") (name "/N$LEDB56") (class "Default")
      (node (ref "IC4") (pin "41") (pinfunction "OUTB14_41") (pintype "bidirectional"))
      (node (ref "LED56") (pin "2") (pinfunction "BLUE_2") (pintype "bidirectional"))
    )
    (net (code "83") (name "/N$LEDB57") (class "Default")
      (node (ref "IC4") (pin "13") (pinfunction "OUTB1_13") (pintype "bidirectional"))
      (node (ref "LED57") (pin "2") (pinfunction "BLUE_2") (pintype "bidirectional"))
    )
    (net (code "84") (name "/N$LEDB58") (class "Default")
      (node (ref "IC4") (pin "10") (pinfunction "OUTB5_10") (pintype "bidirectional"))
      (node (ref "LED58") (pin "2") (pinfunction "BLUE_2") (pintype "bidirectional"))
    )
    (net (code "85") (name "/N$LEDB59") (class "Default")
      (node (ref "IC4") (pin "44") (pinfunction "OUTB13_44") (pintype "bidirectional"))
      (node (ref "LED59") (pin "2") (pinfunction "BLUE_2") (pintype "bidirectional"))
    )
    (net (code "86") (name "/N$LEDB60") (class "Default")
      (node (ref "IC4") (pin "47") (pinfunction "OUTB9_47") (pintype "bidirectional"))
      (node (ref "LED60") (pin "2") (pinfunction "BLUE_2") (pintype "bidirectional"))
    )
    (net (code "87") (name "/N$LEDB61") (class "Default")
      (node (ref "IC4") (pin "4") (pinfunction "OUTB4_4") (pintype "bidirectional"))
      (node (ref "LED61") (pin "2") (pinfunction "BLUE_2") (pintype "bidirectional"))
    )
    (net (code "88") (name "/N$LEDB62") (class "Default")
      (node (ref "IC4") (pin "7") (pinfunction "OUTB0_7") (pintype "bidirectional"))
      (node (ref "LED62") (pin "2") (pinfunction "BLUE_2") (pintype "bidirectional"))
    )
    (net (code "89") (name "/N$LEDB63") (class "Default")
      (node (ref "IC4") (pin "50") (pinfunction "OUTB12_50") (pintype "bidirectional"))
      (node (ref "LED63") (pin "2") (pinfunction "BLUE_2") (pintype "bidirectional"))
    )
    (net (code "90") (name "/N$LEDB64") (class "Default")
      (node (ref "IC4") (pin "53") (pinfunction "OUTB8_53") (pintype "bidirectional"))
      (node (ref "LED64") (pin "2") (pinfunction "BLUE_2") (pintype "bidirectional"))
    )
    (net (code "91") (name "/N$LEDB65") (class "Default")
      (node (ref "IC5") (pin "25") (pinfunction "OUTB7_25") (pintype "bidirectional"))
      (node (ref "LED65") (pin "2") (pinfunction "BLUE_2") (pintype "bidirectional"))
    )
    (net (code "92") (name "/N$LEDB66") (class "Default")
      (node (ref "IC5") (pin "22") (pinfunction "OUTB3_22") (pintype "bidirectional"))
      (node (ref "LED66") (pin "2") (pinfunction "BLUE_2") (pintype "bidirectional"))
    )
    (net (code "93") (name "/N$LEDB67") (class "Default")
      (node (ref "IC5") (pin "32") (pinfunction "OUTB11_32") (pintype "bidirectional"))
      (node (ref "LED67") (pin "2") (pinfunction "BLUE_2") (pintype "bidirectional"))
    )
    (net (code "94") (name "/N$LEDB68") (class "Default")
      (node (ref "IC5") (pin "35") (pinfunction "OUTB15_35") (pintype "bidirectional"))
      (node (ref "LED68") (pin "2") (pinfunction "BLUE_2") (pintype "bidirectional"))
    )
    (net (code "95") (name "/N$LEDB69") (class "Default")
      (node (ref "IC5") (pin "19") (pinfunction "OUTB6_19") (pintype "bidirectional"))
      (node (ref "LED69") (pin "2") (pinfunction "BLUE_2") (pintype "bidirectional"))
    )
    (net (code "96") (name "/N$LEDB70") (class "Default")
      (node (ref "IC5") (pin "16") (pinfunction "OUTB2_16") (pintype "bidirectional"))
      (node (ref "LED70") (pin "2") (pinfunction "BLUE_2") (pintype "bidirectional"))
    )
    (net (code "97") (name "/N$LEDB71") (class "Default")
      (node (ref "IC5") (pin "38") (pinfunction "OUTB10_38") (pintype "bidirectional"))
      (node (ref "LED71") (pin "2") (pinfunction "BLUE_2") (pintype "bidirectional"))
    )
    (net (code "98") (name "/N$LEDB72") (class "Default")
      (node (ref "IC5") (pin "41") (pinfunction "OUTB14_41") (pintype "bidirectional"))
      (node (ref "LED72") (pin "2") (pinfunction "BLUE_2") (pintype "bidirectional"))
    )
    (net (code "99") (name "/N$LEDB73") (class "Default")
      (node (ref "IC5") (pin "13") (pinfunction "OUTB1_13") (pintype "bidirectional"))
      (node (ref "LED73") (pin "2") (pinfunction "BLUE_2") (pintype "bidirectional"))
    )
    (net (code "100") (name "/N$LEDB74") (class "Default")
      (node (ref "IC5") (pin "10") (pinfunction "OUTB5_10") (pintype "bidirectional"))
      (node (ref "LED74") (pin "2") (pinfunction "BLUE_2") (pintype "bidirectional"))
    )
    (net (code "101") (name "/N$LEDB75") (class "Default")
      (node (ref "IC5") (pin "44") (pinfunction "OUTB13_44") (pintype "bidirectional"))
      (node (ref "LED75") (pin "2") (pinfunction "BLUE_2") (pintype "bidirectional"))
    )
    (net (code "102") (name "/N$LEDB76") (class "Default")
      (node (ref "IC5") (pin "47") (pinfunction "OUTB9_47") (pintype "bidirectional"))
      (node (ref "LED76") (pin "2") (pinfunction "BLUE_2") (pintype "bidirectional"))
    )
    (net (code "103") (name "/N$LEDB77") (class "Default")
      (node (ref "IC5") (pin "4") (pinfunction "OUTB4_4") (pintype "bidirectional"))
      (node (ref "LED77") (pin "2") (pinfunction "BLUE_2") (pintype "bidirectional"))
    )
    (net (code "104") (name "/N$LEDB78") (class "Default")
      (node (ref "IC5") (pin "7") (pinfunction "OUTB0_7") (pintype "bidirectional"))
      (node (ref "LED78") (pin "2") (pinfunction "BLUE_2") (pintype "bidirectional"))
    )
    (net (code "105") (name "/N$LEDB79") (class "Default")
      (node (ref "IC5") (pin "50") (pinfunction "OUTB12_50") (pintype "bidirectional"))
      (node (ref "LED79") (pin "2") (pinfunction "BLUE_2") (pintype "bidirectional"))
    )
    (net (code "106") (name "/N$LEDB80") (class "Default")
      (node (ref "IC5") (pin "53") (pinfunction "OUTB8_53") (pintype "bidirectional"))
      (node (ref "LED80") (pin "2") (pinfunction "BLUE_2") (pintype "bidirectional"))
    )
    (net (code "107") (name "/N$LEDB81") (class "Default")
      (node (ref "IC6") (pin "25") (pinfunction "OUTB7_25") (pintype "bidirectional"))
      (node (ref "LED81") (pin "2") (pinfunction "BLUE_2") (pintype "bidirectional"))
    )
    (net (code "108") (name "/N$LEDB82") (class "Default")
      (node (ref "IC6") (pin "22") (pinfunction "OUTB3_22") (pintype "bidirectional"))
      (node (ref "LED82") (pin "2") (pinfunction "BLUE_2") (pintype "bidirectional"))
    )
    (net (code "109") (name "/N$LEDB83") (class "Default")
      (node (ref "IC6") (pin "32") (pinfunction "OUTB11_32") (pintype "bidirectional"))
      (node (ref "LED83") (pin "2") (pinfunction "BLUE_2") (pintype "bidirectional"))
    )
    (net (code "110") (name "/N$LEDB84") (class "Default")
      (node (ref "IC6") (pin "35") (pinfunction "OUTB15_35") (pintype "bidirectional"))
      (node (ref "LED84") (pin "2") (pinfunction "BLUE_2") (pintype "bidirectional"))
    )
    (net (code "111") (name "/N$LEDB85") (class "Default")
      (node (ref "IC6") (pin "19") (pinfunction "OUTB6_19") (pintype "bidirectional"))
      (node (ref "LED85") (pin "2") (pinfunction "BLUE_2") (pintype "bidirectional"))
    )
    (net (code "112") (name "/N$LEDB86") (class "Default")
      (node (ref "IC6") (pin "16") (pinfunction "OUTB2_16") (pintype "bidirectional"))
      (node (ref "LED86") (pin "2") (pinfunction "BLUE_2") (pintype "bidirectional"))
    )
    (net (code "113") (name "/N$LEDB87") (class "Default")
      (node (ref "IC6") (pin "38") (pinfunction "OUTB10_38") (pintype "bidirectional"))
      (node (ref "LED87") (pin "2") (pinfunction "BLUE_2") (pintype "bidirectional"))
    )
    (net (code "114") (name "/N$LEDB88") (class "Default")
      (node (ref "IC6") (pin "41") (pinfunction "OUTB14_41") (pintype "bidirectional"))
      (node (ref "LED88") (pin "2") (pinfunction "BLUE_2") (pintype "bidirectional"))
    )
    (net (code "115") (name "/N$LEDB89") (class "Default")
      (node (ref "IC6") (pin "13") (pinfunction "OUTB1_13") (pintype "bidirectional"))
      (node (ref "LED89") (pin "2") (pinfunction "BLUE_2") (pintype "bidirectional"))
    )
    (net (code "116") (name "/N$LEDB90") (class "Default")
      (node (ref "IC6") (pin "10") (pinfunction "OUTB5_10") (pintype "bidirectional"))
      (node (ref "LED90") (pin "2") (pinfunction "BLUE_2") (pintype "bidirectional"))
    )
    (net (code "117") (name "/N$LEDB91") (class "Default")
      (node (ref "IC6") (pin "44") (pinfunction "OUTB13_44") (pintype "bidirectional"))
      (node (ref "LED91") (pin "2") (pinfunction "BLUE_2") (pintype "bidirectional"))
    )
    (net (code "118") (name "/N$LEDB92") (class "Default")
      (node (ref "IC6") (pin "47") (pinfunction "OUTB9_47") (pintype "bidirectional"))
      (node (ref "LED92") (pin "2") (pinfunction "BLUE_2") (pintype "bidirectional"))
    )
    (net (code "119") (name "/N$LEDB93") (class "Default")
      (node (ref "IC6") (pin "4") (pinfunction "OUTB4_4") (pintype "bidirectional"))
      (node (ref "LED93") (pin "2") (pinfunction "BLUE_2") (pintype "bidirectional"))
    )
    (net (code "120") (name "/N$LEDB94") (class "Default")
      (node (ref "IC6") (pin "7") (pinfunction "OUTB0_7") (pintype "bidirectional"))
      (node (ref "LED94") (pin "2") (pinfunction "BLUE_2") (pintype "bidirectional"))
    )
    (net (code "121") (name "/N$LEDB95") (class "Default")
      (node (ref "IC6") (pin "50") (pinfunction "OUTB12_50") (pintype "bidirectional"))
      (node (ref "LED95") (pin "2") (pinfunction "BLUE_2") (pintype "bidirectional"))
    )
    (net (code "122") (name "/N$LEDB96") (class "Default")
      (node (ref "IC6") (pin "53") (pinfunction "OUTB8_53") (pintype "bidirectional"))
      (node (ref "LED96") (pin "2") (pinfunction "BLUE_2") (pintype "bidirectional"))
    )
    (net (code "123") (name "/N$LEDB97") (class "Default")
      (node (ref "IC7") (pin "25") (pinfunction "OUTB7_25") (pintype "bidirectional"))
      (node (ref "LED97") (pin "2") (pinfunction "BLUE_2") (pintype "bidirectional"))
    )
    (net (code "124") (name "/N$LEDB98") (class "Default")
      (node (ref "IC7") (pin "22") (pinfunction "OUTB3_22") (pintype "bidirectional"))
      (node (ref "LED98") (pin "2") (pinfunction "BLUE_2") (pintype "bidirectional"))
    )
    (net (code "125") (name "/N$LEDB99") (class "Default")
      (node (ref "IC7") (pin "32") (pinfunction "OUTB11_32") (pintype "bidirectional"))
      (node (ref "LED99") (pin "2") (pinfunction "BLUE_2") (pintype "bidirectional"))
    )
    (net (code "126") (name "/N$LEDB100") (class "Default")
      (node (ref "IC7") (pin "35") (pinfunction "OUTB15_35") (pintype "bidirectional"))
      (node (ref "LED100") (pin "2") (pinfunction "BLUE_2") (pintype "bidirectional"))
    )
    (net (code "127") (name "/N$LEDB101") (class "Default")
      (node (ref "IC7") (pin "19") (pinfunction "OUTB6_19") (pintype "bidirectional"))
      (node (ref "LED101") (pin "2") (pinfunction "BLUE_2") (pintype "bidirectional"))
    )
    (net (code "128") (name "/N$LEDB102") (class "Default")
      (node (ref "IC7") (pin "16") (pinfunction "OUTB2_16") (pintype "bidirectional"))
      (node (ref "LED102") (pin "2") (pinfunction "BLUE_2") (pintype "bidirectional"))
    )
    (net (code "129") (name "/N$LEDB103") (class "Default")
      (node (ref "IC7") (pin "38") (pinfunction "OUTB10_38") (pintype "bidirectional"))
      (node (ref "LED103") (pin "2") (pinfunction "BLUE_2") (pintype "bidirectional"))
    )
    (net (code "130") (name "/N$LEDB104") (class "Default")
      (node (ref "IC7") (pin "41") (pinfunction "OUTB14_41") (pintype "bidirectional"))
      (node (ref "LED104") (pin "2") (pinfunction "BLUE_2") (pintype "bidirectional"))
    )
    (net (code "131") (name "/N$LEDB105") (class "Default")
      (node (ref "IC7") (pin "13") (pinfunction "OUTB1_13") (pintype "bidirectional"))
      (node (ref "LED105") (pin "2") (pinfunction "BLUE_2") (pintype "bidirectional"))
    )
    (net (code "132") (name "/N$LEDB106") (class "Default")
      (node (ref "IC7") (pin "10") (pinfunction "OUTB5_10") (pintype "bidirectional"))
      (node (ref "LED106") (pin "2") (pinfunction "BLUE_2") (pintype "bidirectional"))
    )
    (net (code "133") (name "/N$LEDB107") (class "Default")
      (node (ref "IC7") (pin "44") (pinfunction "OUTB13_44") (pintype "bidirectional"))
      (node (ref "LED107") (pin "2") (pinfunction "BLUE_2") (pintype "bidirectional"))
    )
    (net (code "134") (name "/N$LEDB108") (class "Default")
      (node (ref "IC7") (pin "47") (pinfunction "OUTB9_47") (pintype "bidirectional"))
      (node (ref "LED108") (pin "2") (pinfunction "BLUE_2") (pintype "bidirectional"))
    )
    (net (code "135") (name "/N$LEDB109") (class "Default")
      (node (ref "IC7") (pin "4") (pinfunction "OUTB4_4") (pintype "bidirectional"))
      (node (ref "LED109") (pin "2") (pinfunction "BLUE_2") (pintype "bidirectional"))
    )
    (net (code "136") (name "/N$LEDB110") (class "Default")
      (node (ref "IC7") (pin "7") (pinfunction "OUTB0_7") (pintype "bidirectional"))
      (node (ref "LED110") (pin "2") (pinfunction "BLUE_2") (pintype "bidirectional"))
    )
    (net (code "137") (name "/N$LEDB111") (class "Default")
      (node (ref "IC7") (pin "50") (pinfunction "OUTB12_50") (pintype "bidirectional"))
      (node (ref "LED111") (pin "2") (pinfunction "BLUE_2") (pintype "bidirectional"))
    )
    (net (code "138") (name "/N$LEDB112") (class "Default")
      (node (ref "IC7") (pin "53") (pinfunction "OUTB8_53") (pintype "bidirectional"))
      (node (ref "LED112") (pin "2") (pinfunction "BLUE_2") (pintype "bidirectional"))
    )
    (net (code "139") (name "/N$LEDB113") (class "Default")
      (node (ref "IC8") (pin "25") (pinfunction "OUTB7_25") (pintype "bidirectional"))
      (node (ref "LED113") (pin "2") (pinfunction "BLUE_2") (pintype "bidirectional"))
    )
    (net (code "140") (name "/N$LEDB114") (class "Default")
      (node (ref "IC8") (pin "22") (pinfunction "OUTB3_22") (pintype "bidirectional"))
      (node (ref "LED114") (pin "2") (pinfunction "BLUE_2") (pintype "bidirectional"))
    )
    (net (code "141") (name "/N$LEDB115") (class "Default")
      (node (ref "IC8") (pin "32") (pinfunction "OUTB11_32") (pintype "bidirectional"))
      (node (ref "LED115") (pin "2") (pinfunction "BLUE_2") (pintype "bidirectional"))
    )
    (net (code "142") (name "/N$LEDB116") (class "Default")
      (node (ref "IC8") (pin "35") (pinfunction "OUTB15_35") (pintype "bidirectional"))
      (node (ref "LED116") (pin "2") (pinfunction "BLUE_2") (pintype "bidirectional"))
    )
    (net (code "143") (name "/N$LEDB117") (class "Default")
      (node (ref "IC8") (pin "19") (pinfunction "OUTB6_19") (pintype "bidirectional"))
      (node (ref "LED117") (pin "2") (pinfunction "BLUE_2") (pintype "bidirectional"))
    )
    (net (code "144") (name "/N$LEDB118") (class "Default")
      (node (ref "IC8") (pin "16") (pinfunction "OUTB2_16") (pintype "bidirectional"))
      (node (ref "LED118") (pin "2") (pinfunction "BLUE_2") (pintype "bidirectional"))
    )
    (net (code "145") (name "/N$LEDB119") (class "Default")
      (node (ref "IC8") (pin "38") (pinfunction "OUTB10_38") (pintype "bidirectional"))
      (node (ref "LED119") (pin "2") (pinfunction "BLUE_2") (pintype "bidirectional"))
    )
    (net (code "146") (name "/N$LEDB120") (class "Default")
      (node (ref "IC8") (pin "41") (pinfunction "OUTB14_41") (pintype "bidirectional"))
      (node (ref "LED120") (pin "2") (pinfunction "BLUE_2") (pintype "bidirectional"))
    )
    (net (code "147") (name "/N$LEDG1") (class "Default")
      (node (ref "IC1") (pin "27") (pinfunction "OUTG7_27") (pintype "bidirectional"))
      (node (ref "LED1") (pin "1") (pinfunction "GREEN_1") (pintype "bidirectional"))
    )
    (net (code "148") (name "/N$LEDG2") (class "Default")
      (node (ref "IC1") (pin "24") (pinfunction "OUTG3_24") (pintype "bidirectional"))
      (node (ref "LED2") (pin "1") (pinfunction "GREEN_1") (pintype "bidirectional"))
    )
    (net (code "149") (name "/N$LEDG3") (class "Default")
      (node (ref "IC1") (pin "30") (pinfunction "OUTG11_30") (pintype "bidirectional"))
      (node (ref "LED3") (pin "1") (pinfunction "GREEN_1") (pintype "bidirectional"))
    )
    (net (code "150") (name "/N$LEDG4") (class "Default")
      (node (ref "IC1") (pin "33") (pinfunction "OUTG15_33") (pintype "bidirectional"))
      (node (ref "LED4") (pin "1") (pinfunction "GREEN_1") (pintype "bidirectional"))
    )
    (net (code "151") (name "/N$LEDG5") (class "Default")
      (node (ref "IC1") (pin "21") (pinfunction "OUTG6_21") (pintype "bidirectional"))
      (node (ref "LED5") (pin "1") (pinfunction "GREEN_1") (pintype "bidirectional"))
    )
    (net (code "152") (name "/N$LEDG6") (class "Default")
      (node (ref "IC1") (pin "18") (pinfunction "OUTG2_18") (pintype "bidirectional"))
      (node (ref "LED6") (pin "1") (pinfunction "GREEN_1") (pintype "bidirectional"))
    )
    (net (code "153") (name "/N$LEDG7") (class "Default")
      (node (ref "IC1") (pin "36") (pinfunction "OUTG10_36") (pintype "bidirectional"))
      (node (ref "LED7") (pin "1") (pinfunction "GREEN_1") (pintype "bidirectional"))
    )
    (net (code "154") (name "/N$LEDG8") (class "Default")
      (node (ref "IC1") (pin "39") (pinfunction "OUTG14_39") (pintype "bidirectional"))
      (node (ref "LED8") (pin "1") (pinfunction "GREEN_1") (pintype "bidirectional"))
    )
    (net (code "155") (name "/N$LEDG9") (class "Default")
      (node (ref "IC1") (pin "15") (pinfunction "OUTG1_15") (pintype "bidirectional"))
      (node (ref "LED9") (pin "1") (pinfunction "GREEN_1") (pintype "bidirectional"))
    )
    (net (code "156") (name "/N$LEDG10") (class "Default")
      (node (ref "IC1") (pin "12") (pinfunction "OUTG5_12") (pintype "bidirectional"))
      (node (ref "LED10") (pin "1") (pinfunction "GREEN_1") (pintype "bidirectional"))
    )
    (net (code "157") (name "/N$LEDG11") (class "Default")
      (node (ref "IC1") (pin "42") (pinfunction "OUTG13_42") (pintype "bidirectional"))
      (node (ref "LED11") (pin "1") (pinfunction "GREEN_1") (pintype "bidirectional"))
    )
    (net (code "158") (name "/N$LEDG12") (class "Default")
      (node (ref "IC1") (pin "45") (pinfunction "OUTG9_45") (pintype "bidirectional"))
      (node (ref "LED12") (pin "1") (pinfunction "GREEN_1") (pintype "bidirectional"))
    )
    (net (code "159") (name "/N$LEDG13") (class "Default")
      (node (ref "IC1") (pin "6") (pinfunction "OUTG4_6") (pintype "bidirectional"))
      (node (ref "LED13") (pin "1") (pinfunction "GREEN_1") (pintype "bidirectional"))
    )
    (net (code "160") (name "/N$LEDG14") (class "Default")
      (node (ref "IC1") (pin "9") (pinfunction "OUTG0_9") (pintype "bidirectional"))
      (node (ref "LED14") (pin "1") (pinfunction "GREEN_1") (pintype "bidirectional"))
    )
    (net (code "161") (name "/N$LEDG15") (class "Default")
      (node (ref "IC1") (pin "48") (pinfunction "OUTG12_48") (pintype "bidirectional"))
      (node (ref "LED15") (pin "1") (pinfunction "GREEN_1") (pintype "bidirectional"))
    )
    (net (code "162") (name "/N$LEDG16") (class "Default")
      (node (ref "IC1") (pin "51") (pinfunction "OUTG8_51") (pintype "bidirectional"))
      (node (ref "LED16") (pin "1") (pinfunction "GREEN_1") (pintype "bidirectional"))
    )
    (net (code "163") (name "/N$LEDG17") (class "Default")
      (node (ref "IC2") (pin "27") (pinfunction "OUTG7_27") (pintype "bidirectional"))
      (node (ref "LED17") (pin "1") (pinfunction "GREEN_1") (pintype "bidirectional"))
    )
    (net (code "164") (name "/N$LEDG18") (class "Default")
      (node (ref "IC2") (pin "24") (pinfunction "OUTG3_24") (pintype "bidirectional"))
      (node (ref "LED18") (pin "1") (pinfunction "GREEN_1") (pintype "bidirectional"))
    )
    (net (code "165") (name "/N$LEDG19") (class "Default")
      (node (ref "IC2") (pin "30") (pinfunction "OUTG11_30") (pintype "bidirectional"))
      (node (ref "LED19") (pin "1") (pinfunction "GREEN_1") (pintype "bidirectional"))
    )
    (net (code "166") (name "/N$LEDG20") (class "Default")
      (node (ref "IC2") (pin "33") (pinfunction "OUTG15_33") (pintype "bidirectional"))
      (node (ref "LED20") (pin "1") (pinfunction "GREEN_1") (pintype "bidirectional"))
    )
    (net (code "167") (name "/N$LEDG21") (class "Default")
      (node (ref "IC2") (pin "21") (pinfunction "OUTG6_21") (pintype "bidirectional"))
      (node (ref "LED21") (pin "1") (pinfunction "GREEN_1") (pintype "bidirectional"))
    )
    (net (code "168") (name "/N$LEDG22") (class "Default")
      (node (ref "IC2") (pin "18") (pinfunction "OUTG2_18") (pintype "bidirectional"))
      (node (ref "LED22") (pin "1") (pinfunction "GREEN_1") (pintype "bidirectional"))
    )
    (net (code "169") (name "/N$LEDG23") (class "Default")
      (node (ref "IC2") (pin "36") (pinfunction "OUTG10_36") (pintype "bidirectional"))
      (node (ref "LED23") (pin "1") (pinfunction "GREEN_1") (pintype "bidirectional"))
    )
    (net (code "170") (name "/N$LEDG24") (class "Default")
      (node (ref "IC2") (pin "39") (pinfunction "OUTG14_39") (pintype "bidirectional"))
      (node (ref "LED24") (pin "1") (pinfunction "GREEN_1") (pintype "bidirectional"))
    )
    (net (code "171") (name "/N$LEDG25") (class "Default")
      (node (ref "IC2") (pin "15") (pinfunction "OUTG1_15") (pintype "bidirectional"))
      (node (ref "LED25") (pin "1") (pinfunction "GREEN_1") (pintype "bidirectional"))
    )
    (net (code "172") (name "/N$LEDG26") (class "Default")
      (node (ref "IC2") (pin "12") (pinfunction "OUTG5_12") (pintype "bidirectional"))
      (node (ref "LED26") (pin "1") (pinfunction "GREEN_1") (pintype "bidirectional"))
    )
    (net (code "173") (name "/N$LEDG27") (class "Default")
      (node (ref "IC2") (pin "42") (pinfunction "OUTG13_42") (pintype "bidirectional"))
      (node (ref "LED27") (pin "1") (pinfunction "GREEN_1") (pintype "bidirectional"))
    )
    (net (code "174") (name "/N$LEDG28") (class "Default")
      (node (ref "IC2") (pin "45") (pinfunction "OUTG9_45") (pintype "bidirectional"))
      (node (ref "LED28") (pin "1") (pinfunction "GREEN_1") (pintype "bidirectional"))
    )
    (net (code "175") (name "/N$LEDG29") (class "Default")
      (node (ref "IC2") (pin "6") (pinfunction "OUTG4_6") (pintype "bidirectional"))
      (node (ref "LED29") (pin "1") (pinfunction "GREEN_1") (pintype "bidirectional"))
    )
    (net (code "176") (name "/N$LEDG30") (class "Default")
      (node (ref "IC2") (pin "9") (pinfunction "OUTG0_9") (pintype "bidirectional"))
      (node (ref "LED30") (pin "1") (pinfunction "GREEN_1") (pintype "bidirectional"))
    )
    (net (code "177") (name "/N$LEDG31") (class "Default")
      (node (ref "IC2") (pin "48") (pinfunction "OUTG12_48") (pintype "bidirectional"))
      (node (ref "LED31") (pin "1") (pinfunction "GREEN_1") (pintype "bidirectional"))
    )
    (net (code "178") (name "/N$LEDG32") (class "Default")
      (node (ref "IC2") (pin "51") (pinfunction "OUTG8_51") (pintype "bidirectional"))
      (node (ref "LED32") (pin "1") (pinfunction "GREEN_1") (pintype "bidirectional"))
    )
    (net (code "179") (name "/N$LEDG33") (class "Default")
      (node (ref "IC3") (pin "27") (pinfunction "OUTG7_27") (pintype "bidirectional"))
      (node (ref "LED33") (pin "1") (pinfunction "GREEN_1") (pintype "bidirectional"))
    )
    (net (code "180") (name "/N$LEDG34") (class "Default")
      (node (ref "IC3") (pin "24") (pinfunction "OUTG3_24") (pintype "bidirectional"))
      (node (ref "LED34") (pin "1") (pinfunction "GREEN_1") (pintype "bidirectional"))
    )
    (net (code "181") (name "/N$LEDG35") (class "Default")
      (node (ref "IC3") (pin "30") (pinfunction "OUTG11_30") (pintype "bidirectional"))
      (node (ref "LED35") (pin "1") (pinfunction "GREEN_1") (pintype "bidirectional"))
    )
    (net (code "182") (name "/N$LEDG36") (class "Default")
      (node (ref "IC3") (pin "33") (pinfunction "OUTG15_33") (pintype "bidirectional"))
      (node (ref "LED36") (pin "1") (pinfunction "GREEN_1") (pintype "bidirectional"))
    )
    (net (code "183") (name "/N$LEDG37") (class "Default")
      (node (ref "IC3") (pin "21") (pinfunction "OUTG6_21") (pintype "bidirectional"))
      (node (ref "LED37") (pin "1") (pinfunction "GREEN_1") (pintype "bidirectional"))
    )
    (net (code "184") (name "/N$LEDG38") (class "Default")
      (node (ref "IC3") (pin "18") (pinfunction "OUTG2_18") (pintype "bidirectional"))
      (node (ref "LED38") (pin "1") (pinfunction "GREEN_1") (pintype "bidirectional"))
    )
    (net (code "185") (name "/N$LEDG39") (class "Default")
      (node (ref "IC3") (pin "36") (pinfunction "OUTG10_36") (pintype "bidirectional"))
      (node (ref "LED39") (pin "1") (pinfunction "GREEN_1") (pintype "bidirectional"))
    )
    (net (code "186") (name "/N$LEDG40") (class "Default")
      (node (ref "IC3") (pin "39") (pinfunction "OUTG14_39") (pintype "bidirectional"))
      (node (ref "LED40") (pin "1") (pinfunction "GREEN_1") (pintype "bidirectional"))
    )
    (net (code "187") (name "/N$LEDG41") (class "Default")
      (node (ref "IC3") (pin "15") (pinfunction "OUTG1_15") (pintype "bidirectional"))
      (node (ref "LED41") (pin "1") (pinfunction "GREEN_1") (pintype "bidirectional"))
    )
    (net (code "188") (name "/N$LEDG42") (class "Default")
      (node (ref "IC3") (pin "12") (pinfunction "OUTG5_12") (pintype "bidirectional"))
      (node (ref "LED42") (pin "1") (pinfunction "GREEN_1") (pintype "bidirectional"))
    )
    (net (code "189") (name "/N$LEDG43") (class "Default")
      (node (ref "IC3") (pin "42") (pinfunction "OUTG13_42") (pintype "bidirectional"))
      (node (ref "LED43") (pin "1") (pinfunction "GREEN_1") (pintype "bidirectional"))
    )
    (net (code "190") (name "/N$LEDG44") (class "Default")
      (node (ref "IC3") (pin "45") (pinfunction "OUTG9_45") (pintype "bidirectional"))
      (node (ref "LED44") (pin "1") (pinfunction "GREEN_1") (pintype "bidirectional"))
    )
    (net (code "191") (name "/N$LEDG45") (class "Default")
      (node (ref "IC3") (pin "6") (pinfunction "OUTG4_6") (pintype "bidirectional"))
      (node (ref "LED45") (pin "1") (pinfunction "GREEN_1") (pintype "bidirectional"))
    )
    (net (code "192") (name "/N$LEDG46") (class "Default")
      (node (ref "IC3") (pin "9") (pinfunction "OUTG0_9") (pintype "bidirectional"))
      (node (ref "LED46") (pin "1") (pinfunction "GREEN_1") (pintype "bidirectional"))
    )
    (net (code "193") (name "/N$LEDG47") (class "Default")
      (node (ref "IC3") (pin "48") (pinfunction "OUTG12_48") (pintype "bidirectional"))
      (node (ref "LED47") (pin "1") (pinfunction "GREEN_1") (pintype "bidirectional"))
    )
    (net (code "194") (name "/N$LEDG48") (class "Default")
      (node (ref "IC3") (pin "51") (pinfunction "OUTG8_51") (pintype "bidirectional"))
      (node (ref "LED48") (pin "1") (pinfunction "GREEN_1") (pintype "bidirectional"))
    )
    (net (code "195") (name "/N$LEDG49") (class "Default")
      (node (ref "IC4") (pin "27") (pinfunction "OUTG7_27") (pintype "bidirectional"))
      (node (ref "LED49") (pin "1") (pinfunction "GREEN_1") (pintype "bidirectional"))
    )
    (net (code "196") (name "/N$LEDG50") (class "Default")
      (node (ref "IC4") (pin "24") (pinfunction "OUTG3_24") (pintype "bidirectional"))
      (node (ref "LED50") (pin "1") (pinfunction "GREEN_1") (pintype "bidirectional"))
    )
    (net (code "197") (name "/N$LEDG51") (class "Default")
      (node (ref "IC4") (pin "30") (pinfunction "OUTG11_30") (pintype "bidirectional"))
      (node (ref "LED51") (pin "1") (pinfunction "GREEN_1") (pintype "bidirectional"))
    )
    (net (code "198") (name "/N$LEDG52") (class "Default")
      (node (ref "IC4") (pin "33") (pinfunction "OUTG15_33") (pintype "bidirectional"))
      (node (ref "LED52") (pin "1") (pinfunction "GREEN_1") (pintype "bidirectional"))
    )
    (net (code "199") (name "/N$LEDG53") (class "Default")
      (node (ref "IC4") (pin "21") (pinfunction "OUTG6_21") (pintype "bidirectional"))
      (node (ref "LED53") (pin "1") (pinfunction "GREEN_1") (pintype "bidirectional"))
    )
    (net (code "200") (name "/N$LEDG54") (class "Default")
      (node (ref "IC4") (pin "18") (pinfunction "OUTG2_18") (pintype "bidirectional"))
      (node (ref "LED54") (pin "1") (pinfunction "GREEN_1") (pintype "bidirectional"))
    )
    (net (code "201") (name "/N$LEDG55") (class "Default")
      (node (ref "IC4") (pin "36") (pinfunction "OUTG10_36") (pintype "bidirectional"))
      (node (ref "LED55") (pin "1") (pinfunction "GREEN_1") (pintype "bidirectional"))
    )
    (net (code "202") (name "/N$LEDG56") (class "Default")
      (node (ref "IC4") (pin "39") (pinfunction "OUTG14_39") (pintype "bidirectional"))
      (node (ref "LED56") (pin "1") (pinfunction "GREEN_1") (pintype "bidirectional"))
    )
    (net (code "203") (name "/N$LEDG57") (class "Default")
      (node (ref "IC4") (pin "15") (pinfunction "OUTG1_15") (pintype "bidirectional"))
      (node (ref "LED57") (pin "1") (pinfunction "GREEN_1") (pintype "bidirectional"))
    )
    (net (code "204") (name "/N$LEDG58") (class "Default")
      (node (ref "IC4") (pin "12") (pinfunction "OUTG5_12") (pintype "bidirectional"))
      (node (ref "LED58") (pin "1") (pinfunction "GREEN_1") (pintype "bidirectional"))
    )
    (net (code "205") (name "/N$LEDG59") (class "Default")
      (node (ref "IC4") (pin "42") (pinfunction "OUTG13_42") (pintype "bidirectional"))
      (node (ref "LED59") (pin "1") (pinfunction "GREEN_1") (pintype "bidirectional"))
    )
    (net (code "206") (name "/N$LEDG60") (class "Default")
      (node (ref "IC4") (pin "45") (pinfunction "OUTG9_45") (pintype "bidirectional"))
      (node (ref "LED60") (pin "1") (pinfunction "GREEN_1") (pintype "bidirectional"))
    )
    (net (code "207") (name "/N$LEDG61") (class "Default")
      (node (ref "IC4") (pin "6") (pinfunction "OUTG4_6") (pintype "bidirectional"))
      (node (ref "LED61") (pin "1") (pinfunction "GREEN_1") (pintype "bidirectional"))
    )
    (net (code "208") (name "/N$LEDG62") (class "Default")
      (node (ref "IC4") (pin "9") (pinfunction "OUTG0_9") (pintype "bidirectional"))
      (node (ref "LED62") (pin "1") (pinfunction "GREEN_1") (pintype "bidirectional"))
    )
    (net (code "209") (name "/N$LEDG63") (class "Default")
      (node (ref "IC4") (pin "48") (pinfunction "OUTG12_48") (pintype "bidirectional"))
      (node (ref "LED63") (pin "1") (pinfunction "GREEN_1") (pintype "bidirectional"))
    )
    (net (code "210") (name "/N$LEDG64") (class "Default")
      (node (ref "IC4") (pin "51") (pinfunction "OUTG8_51") (pintype "bidirectional"))
      (node (ref "LED64") (pin "1") (pinfunction "GREEN_1") (pintype "bidirectional"))
    )
    (net (code "211") (name "/N$LEDG65") (class "Default")
      (node (ref "IC5") (pin "27") (pinfunction "OUTG7_27") (pintype "bidirectional"))
      (node (ref "LED65") (pin "1") (pinfunction "GREEN_1") (pintype "bidirectional"))
    )
    (net (code "212") (name "/N$LEDG66") (class "Default")
      (node (ref "IC5") (pin "24") (pinfunction "OUTG3_24") (pintype "bidirectional"))
      (node (ref "LED66") (pin "1") (pinfunction "GREEN_1") (pintype "bidirectional"))
    )
    (net (code "213") (name "/N$LEDG67") (class "Default")
      (node (ref "IC5") (pin "30") (pinfunction "OUTG11_30") (pintype "bidirectional"))
      (node (ref "LED67") (pin "1") (pinfunction "GREEN_1") (pintype "bidirectional"))
    )
    (net (code "214") (name "/N$LEDG68") (class "Default")
      (node (ref "IC5") (pin "33") (pinfunction "OUTG15_33") (pintype "bidirectional"))
      (node (ref "LED68") (pin "1") (pinfunction "GREEN_1") (pintype "bidirectional"))
    )
    (net (code "215") (name "/N$LEDG69") (class "Default")
      (node (ref "IC5") (pin "21") (pinfunction "OUTG6_21") (pintype "bidirectional"))
      (node (ref "LED69") (pin "1") (pinfunction "GREEN_1") (pintype "bidirectional"))
    )
    (net (code "216") (name "/N$LEDG70") (class "Default")
      (node (ref "IC5") (pin "18") (pinfunction "OUTG2_18") (pintype "bidirectional"))
      (node (ref "LED70") (pin "1") (pinfunction "GREEN_1") (pintype "bidirectional"))
    )
    (net (code "217") (name "/N$LEDG71") (class "Default")
      (node (ref "IC5") (pin "36") (pinfunction "OUTG10_36") (pintype "bidirectional"))
      (node (ref "LED71") (pin "1") (pinfunction "GREEN_1") (pintype "bidirectional"))
    )
    (net (code "218") (name "/N$LEDG72") (class "Default")
      (node (ref "IC5") (pin "39") (pinfunction "OUTG14_39") (pintype "bidirectional"))
      (node (ref "LED72") (pin "1") (pinfunction "GREEN_1") (pintype "bidirectional"))
    )
    (net (code "219") (name "/N$LEDG73") (class "Default")
      (node (ref "IC5") (pin "15") (pinfunction "OUTG1_15") (pintype "bidirectional"))
      (node (ref "LED73") (pin "1") (pinfunction "GREEN_1") (pintype "bidirectional"))
    )
    (net (code "220") (name "/N$LEDG74") (class "Default")
      (node (ref "IC5") (pin "12") (pinfunction "OUTG5_12") (pintype "bidirectional"))
      (node (ref "LED74") (pin "1") (pinfunction "GREEN_1") (pintype "bidirectional"))
    )
    (net (code "221") (name "/N$LEDG75") (class "Default")
      (node (ref "IC5") (pin "42") (pinfunction "OUTG13_42") (pintype "bidirectional"))
      (node (ref "LED75") (pin "1") (pinfunction "GREEN_1") (pintype "bidirectional"))
    )
    (net (code "222") (name "/N$LEDG76") (class "Default")
      (node (ref "IC5") (pin "45") (pinfunction "OUTG9_45") (pintype "bidirectional"))
      (node (ref "LED76") (pin "1") (pinfunction "GREEN_1") (pintype "bidirectional"))
    )
    (net (code "223") (name "/N$LEDG77") (class "Default")
      (node (ref "IC5") (pin "6") (pinfunction "OUTG4_6") (pintype "bidirectional"))
      (node (ref "LED77") (pin "1") (pinfunction "GREEN_1") (pintype "bidirectional"))
    )
    (net (code "224") (name "/N$LEDG78") (class "Default")
      (node (ref "IC5") (pin "9") (pinfunction "OUTG0_9") (pintype "bidirectional"))
      (node (ref "LED78") (pin "1") (pinfunction "GREEN_1") (pintype "bidirectional"))
    )
    (net (code "225") (name "/N$LEDG79") (class "Default")
      (node (ref "IC5") (pin "48") (pinfunction "OUTG12_48") (pintype "bidirectional"))
      (node (ref "LED79") (pin "1") (pinfunction "GREEN_1") (pintype "bidirectional"))
    )
    (net (code "226") (name "/N$LEDG80") (class "Default")
      (node (ref "IC5") (pin "51") (pinfunction "OUTG8_51") (pintype "bidirectional"))
      (node (ref "LED80") (pin "1") (pinfunction "GREEN_1") (pintype "bidirectional"))
    )
    (net (code "227") (name "/N$LEDG81") (class "Default")
      (node (ref "IC6") (pin "27") (pinfunction "OUTG7_27") (pintype "bidirectional"))
      (node (ref "LED81") (pin "1") (pinfunction "GREEN_1") (pintype "bidirectional"))
    )
    (net (code "228") (name "/N$LEDG82") (class "Default")
      (node (ref "IC6") (pin "24") (pinfunction "OUTG3_24") (pintype "bidirectional"))
      (node (ref "LED82") (pin "1") (pinfunction "GREEN_1") (pintype "bidirectional"))
    )
    (net (code "229") (name "/N$LEDG83") (class "Default")
      (node (ref "IC6") (pin "30") (pinfunction "OUTG11_30") (pintype "bidirectional"))
      (node (ref "LED83") (pin "1") (pinfunction "GREEN_1") (pintype "bidirectional"))
    )
    (net (code "230") (name "/N$LEDG84") (class "Default")
      (node (ref "IC6") (pin "33") (pinfunction "OUTG15_33") (pintype "bidirectional"))
      (node (ref "LED84") (pin "1") (pinfunction "GREEN_1") (pintype "bidirectional"))
    )
    (net (code "231") (name "/N$LEDG85") (class "Default")
      (node (ref "IC6") (pin "21") (pinfunction "OUTG6_21") (pintype "bidirectional"))
      (node (ref "LED85") (pin "1") (pinfunction "GREEN_1") (pintype "bidirectional"))
    )
    (net (code "232") (name "/N$LEDG86") (class "Default")
      (node (ref "IC6") (pin "18") (pinfunction "OUTG2_18") (pintype "bidirectional"))
      (node (ref "LED86") (pin "1") (pinfunction "GREEN_1") (pintype "bidirectional"))
    )
    (net (code "233") (name "/N$LEDG87") (class "Default")
      (node (ref "IC6") (pin "36") (pinfunction "OUTG10_36") (pintype "bidirectional"))
      (node (ref "LED87") (pin "1") (pinfunction "GREEN_1") (pintype "bidirectional"))
    )
    (net (code "234") (name "/N$LEDG88") (class "Default")
      (node (ref "IC6") (pin "39") (pinfunction "OUTG14_39") (pintype "bidirectional"))
      (node (ref "LED88") (pin "1") (pinfunction "GREEN_1") (pintype "bidirectional"))
    )
    (net (code "235") (name "/N$LEDG89") (class "Default")
      (node (ref "IC6") (pin "15") (pinfunction "OUTG1_15") (pintype "bidirectional"))
      (node (ref "LED89") (pin "1") (pinfunction "GREEN_1") (pintype "bidirectional"))
    )
    (net (code "236") (name "/N$LEDG90") (class "Default")
      (node (ref "IC6") (pin "12") (pinfunction "OUTG5_12") (pintype "bidirectional"))
      (node (ref "LED90") (pin "1") (pinfunction "GREEN_1") (pintype "bidirectional"))
    )
    (net (code "237") (name "/N$LEDG91") (class "Default")
      (node (ref "IC6") (pin "42") (pinfunction "OUTG13_42") (pintype "bidirectional"))
      (node (ref "LED91") (pin "1") (pinfunction "GREEN_1") (pintype "bidirectional"))
    )
    (net (code "238") (name "/N$LEDG92") (class "Default")
      (node (ref "IC6") (pin "45") (pinfunction "OUTG9_45") (pintype "bidirectional"))
      (node (ref "LED92") (pin "1") (pinfunction "GREEN_1") (pintype "bidirectional"))
    )
    (net (code "239") (name "/N$LEDG93") (class "Default")
      (node (ref "IC6") (pin "6") (pinfunction "OUTG4_6") (pintype "bidirectional"))
      (node (ref "LED93") (pin "1") (pinfunction "GREEN_1") (pintype "bidirectional"))
    )
    (net (code "240") (name "/N$LEDG94") (class "Default")
      (node (ref "IC6") (pin "9") (pinfunction "OUTG0_9") (pintype "bidirectional"))
      (node (ref "LED94") (pin "1") (pinfunction "GREEN_1") (pintype "bidirectional"))
    )
    (net (code "241") (name "/N$LEDG95") (class "Default")
      (node (ref "IC6") (pin "48") (pinfunction "OUTG12_48") (pintype "bidirectional"))
      (node (ref "LED95") (pin "1") (pinfunction "GREEN_1") (pintype "bidirectional"))
    )
    (net (code "242") (name "/N$LEDG96") (class "Default")
      (node (ref "IC6") (pin "51") (pinfunction "OUTG8_51") (pintype "bidirectional"))
      (node (ref "LED96") (pin "1") (pinfunction "GREEN_1") (pintype "bidirectional"))
    )
    (net (code "243") (name "/N$LEDG97") (class "Default")
      (node (ref "IC7") (pin "27") (pinfunction "OUTG7_27") (pintype "bidirectional"))
      (node (ref "LED97") (pin "1") (pinfunction "GREEN_1") (pintype "bidirectional"))
    )
    (net (code "244") (name "/N$LEDG98") (class "Default")
      (node (ref "IC7") (pin "24") (pinfunction "OUTG3_24") (pintype "bidirectional"))
      (node (ref "LED98") (pin "1") (pinfunction "GREEN_1") (pintype "bidirectional"))
    )
    (net (code "245") (name "/N$LEDG99") (class "Default")
      (node (ref "IC7") (pin "30") (pinfunction "OUTG11_30") (pintype "bidirectional"))
      (node (ref "LED99") (pin "1") (pinfunction "GREEN_1") (pintype "bidirectional"))
    )
    (net (code "246") (name "/N$LEDG100") (class "Default")
      (node (ref "IC7") (pin "33") (pinfunction "OUTG15_33") (pintype "bidirectional"))
      (node (ref "LED100") (pin "1") (pinfunction "GREEN_1") (pintype "bidirectional"))
    )
    (net (code "247") (name "/N$LEDG101") (class "Default")
      (node (ref "IC7") (pin "21") (pinfunction "OUTG6_21") (pintype "bidirectional"))
      (node (ref "LED101") (pin "1") (pinfunction "GREEN_1") (pintype "bidirectional"))
    )
    (net (code "248") (name "/N$LEDG102") (class "Default")
      (node (ref "IC7") (pin "18") (pinfunction "OUTG2_18") (pintype "bidirectional"))
      (node (ref "LED102") (pin "1") (pinfunction "GREEN_1") (pintype "bidirectional"))
    )
    (net (code "249") (name "/N$LEDG103") (class "Default")
      (node (ref "IC7") (pin "36") (pinfunction "OUTG10_36") (pintype "bidirectional"))
      (node (ref "LED103") (pin "1") (pinfunction "GREEN_1") (pintype "bidirectional"))
    )
    (net (code "250") (name "/N$LEDG104") (class "Default")
      (node (ref "IC7") (pin "39") (pinfunction "OUTG14_39") (pintype "bidirectional"))
      (node (ref "LED104") (pin "1") (pinfunction "GREEN_1") (pintype "bidirectional"))
    )
    (net (code "251") (name "/N$LEDG105") (class "Default")
      (node (ref "IC7") (pin "15") (pinfunction "OUTG1_15") (pintype "bidirectional"))
      (node (ref "LED105") (pin "1") (pinfunction "GREEN_1") (pintype "bidirectional"))
    )
    (net (code "252") (name "/N$LEDG106") (class "Default")
      (node (ref "IC7") (pin "12") (pinfunction "OUTG5_12") (pintype "bidirectional"))
      (node (ref "LED106") (pin "1") (pinfunction "GREEN_1") (pintype "bidirectional"))
    )
    (net (code "253") (name "/N$LEDG107") (class "Default")
      (node (ref "IC7") (pin "42") (pinfunction "OUTG13_42") (pintype "bidirectional"))
      (node (ref "LED107") (pin "1") (pinfunction "GREEN_1") (pintype "bidirectional"))
    )
    (net (code "254") (name "/N$LEDG108") (class "Default")
      (node (ref "IC7") (pin "45") (pinfunction "OUTG9_45") (pintype "bidirectional"))
      (node (ref "LED108") (pin "1") (pinfunction "GREEN_1") (pintype "bidirectional"))
    )
    (net (code "255") (name "/N$LEDG109") (class "Default")
      (node (ref "IC7") (pin "6") (pinfunction "OUTG4_6") (pintype "bidirectional"))
      (node (ref "LED109") (pin "1") (pinfunction "GREEN_1") (pintype "bidirectional"))
    )
    (net (code "256") (name "/N$LEDG110") (class "Default")
      (node (ref "IC7") (pin "9") (pinfunction "OUTG0_9") (pintype "bidirectional"))
      (node (ref "LED110") (pin "1") (pinfunction "GREEN_1") (pintype "bidirectional"))
    )
    (net (code "257") (name "/N$LEDG111") (class "Default")
      (node (ref "IC7") (pin "48") (pinfunction "OUTG12_48") (pintype "bidirectional"))
      (node (ref "LED111") (pin "1") (pinfunction "GREEN_1") (pintype "bidirectional"))
    )
    (net (code "258") (name "/N$LEDG112") (class "Default")
      (node (ref "IC7") (pin "51") (pinfunction "OUTG8_51") (pintype "bidirectional"))
      (node (ref "LED112") (pin "1") (pinfunction "GREEN_1") (pintype "bidirectional"))
    )
    (net (code "259") (name "/N$LEDG113") (class "Default")
      (node (ref "IC8") (pin "27") (pinfunction "OUTG7_27") (pintype "bidirectional"))
      (node (ref "LED113") (pin "1") (pinfunction "GREEN_1") (pintype "bidirectional"))
    )
    (net (code "260") (name "/N$LEDG114") (class "Default")
      (node (ref "IC8") (pin "24") (pinfunction "OUTG3_24") (pintype "bidirectional"))
      (node (ref "LED114") (pin "1") (pinfunction "GREEN_1") (pintype "bidirectional"))
    )
    (net (code "261") (name "/N$LEDG115") (class "Default")
      (node (ref "IC8") (pin "30") (pinfunction "OUTG11_30") (pintype "bidirectional"))
      (node (ref "LED115") (pin "1") (pinfunction "GREEN_1") (pintype "bidirectional"))
    )
    (net (code "262") (name "/N$LEDG116") (class "Default")
      (node (ref "IC8") (pin "33") (pinfunction "OUTG15_33") (pintype "bidirectional"))
      (node (ref "LED116") (pin "1") (pinfunction "GREEN_1") (pintype "bidirectional"))
    )
    (net (code "263") (name "/N$LEDG117") (class "Default")
      (node (ref "IC8") (pin "21") (pinfunction "OUTG6_21") (pintype "bidirectional"))
      (node (ref "LED117") (pin "1") (pinfunction "GREEN_1") (pintype "bidirectional"))
    )
    (net (code "264") (name "/N$LEDG118") (class "Default")
      (node (ref "IC8") (pin "18") (pinfunction "OUTG2_18") (pintype "bidirectional"))
      (node (ref "LED118") (pin "1") (pinfunction "GREEN_1") (pintype "bidirectional"))
    )
    (net (code "265") (name "/N$LEDG119") (class "Default")
      (node (ref "IC8") (pin "36") (pinfunction "OUTG10_36") (pintype "bidirectional"))
      (node (ref "LED119") (pin "1") (pinfunction "GREEN_1") (pintype "bidirectional"))
    )
    (net (code "266") (name "/N$LEDG120") (class "Default")
      (node (ref "IC8") (pin "39") (pinfunction "OUTG14_39") (pintype "bidirectional"))
      (node (ref "LED120") (pin "1") (pinfunction "GREEN_1") (pintype "bidirectional"))
    )
    (net (code "267") (name "/N$LEDR1") (class "Default")
      (node (ref "IC1") (pin "26") (pinfunction "OUTR7_26") (pintype "bidirectional"))
      (node (ref "LED1") (pin "4") (pinfunction "RED_4") (pintype "bidirectional"))
    )
    (net (code "268") (name "/N$LEDR2") (class "Default")
      (node (ref "IC1") (pin "23") (pinfunction "OUTR3_23") (pintype "bidirectional"))
      (node (ref "LED2") (pin "4") (pinfunction "RED_4") (pintype "bidirectional"))
    )
    (net (code "269") (name "/N$LEDR3") (class "Default")
      (node (ref "IC1") (pin "31") (pinfunction "OUTR11_31") (pintype "bidirectional"))
      (node (ref "LED3") (pin "4") (pinfunction "RED_4") (pintype "bidirectional"))
    )
    (net (code "270") (name "/N$LEDR4") (class "Default")
      (node (ref "IC1") (pin "34") (pinfunction "OUTR15_34") (pintype "bidirectional"))
      (node (ref "LED4") (pin "4") (pinfunction "RED_4") (pintype "bidirectional"))
    )
    (net (code "271") (name "/N$LEDR5") (class "Default")
      (node (ref "IC1") (pin "20") (pinfunction "OUTR6_20") (pintype "bidirectional"))
      (node (ref "LED5") (pin "4") (pinfunction "RED_4") (pintype "bidirectional"))
    )
    (net (code "272") (name "/N$LEDR6") (class "Default")
      (node (ref "IC1") (pin "17") (pinfunction "OUTR2_17") (pintype "bidirectional"))
      (node (ref "LED6") (pin "4") (pinfunction "RED_4") (pintype "bidirectional"))
    )
    (net (code "273") (name "/N$LEDR7") (class "Default")
      (node (ref "IC1") (pin "37") (pinfunction "OUTR10_37") (pintype "bidirectional"))
      (node (ref "LED7") (pin "4") (pinfunction "RED_4") (pintype "bidirectional"))
    )
    (net (code "274") (name "/N$LEDR8") (class "Default")
      (node (ref "IC1") (pin "40") (pinfunction "OUTR14_40") (pintype "bidirectional"))
      (node (ref "LED8") (pin "4") (pinfunction "RED_4") (pintype "bidirectional"))
    )
    (net (code "275") (name "/N$LEDR9") (class "Default")
      (node (ref "IC1") (pin "14") (pinfunction "OUTR1_14") (pintype "bidirectional"))
      (node (ref "LED9") (pin "4") (pinfunction "RED_4") (pintype "bidirectional"))
    )
    (net (code "276") (name "/N$LEDR10") (class "Default")
      (node (ref "IC1") (pin "11") (pinfunction "OUTR5_11") (pintype "bidirectional"))
      (node (ref "LED10") (pin "4") (pinfunction "RED_4") (pintype "bidirectional"))
    )
    (net (code "277") (name "/N$LEDR11") (class "Default")
      (node (ref "IC1") (pin "43") (pinfunction "OUTR13_43") (pintype "bidirectional"))
      (node (ref "LED11") (pin "4") (pinfunction "RED_4") (pintype "bidirectional"))
    )
    (net (code "278") (name "/N$LEDR12") (class "Default")
      (node (ref "IC1") (pin "46") (pinfunction "OUTR9_46") (pintype "bidirectional"))
      (node (ref "LED12") (pin "4") (pinfunction "RED_4") (pintype "bidirectional"))
    )
    (net (code "279") (name "/N$LEDR13") (class "Default")
      (node (ref "IC1") (pin "5") (pinfunction "OUTR4_5") (pintype "bidirectional"))
      (node (ref "LED13") (pin "4") (pinfunction "RED_4") (pintype "bidirectional"))
    )
    (net (code "280") (name "/N$LEDR14") (class "Default")
      (node (ref "IC1") (pin "8") (pinfunction "OUTR0_8") (pintype "bidirectional"))
      (node (ref "LED14") (pin "4") (pinfunction "RED_4") (pintype "bidirectional"))
    )
    (net (code "281") (name "/N$LEDR15") (class "Default")
      (node (ref "IC1") (pin "49") (pinfunction "OUTR12_49") (pintype "bidirectional"))
      (node (ref "LED15") (pin "4") (pinfunction "RED_4") (pintype "bidirectional"))
    )
    (net (code "282") (name "/N$LEDR16") (class "Default")
      (node (ref "IC1") (pin "52") (pinfunction "OUTR8_52") (pintype "bidirectional"))
      (node (ref "LED16") (pin "4") (pinfunction "RED_4") (pintype "bidirectional"))
    )
    (net (code "283") (name "/N$LEDR17") (class "Default")
      (node (ref "IC2") (pin "26") (pinfunction "OUTR7_26") (pintype "bidirectional"))
      (node (ref "LED17") (pin "4") (pinfunction "RED_4") (pintype "bidirectional"))
    )
    (net (code "284") (name "/N$LEDR18") (class "Default")
      (node (ref "IC2") (pin "23") (pinfunction "OUTR3_23") (pintype "bidirectional"))
      (node (ref "LED18") (pin "4") (pinfunction "RED_4") (pintype "bidirectional"))
    )
    (net (code "285") (name "/N$LEDR19") (class "Default")
      (node (ref "IC2") (pin "31") (pinfunction "OUTR11_31") (pintype "bidirectional"))
      (node (ref "LED19") (pin "4") (pinfunction "RED_4") (pintype "bidirectional"))
    )
    (net (code "286") (name "/N$LEDR20") (class "Default")
      (node (ref "IC2") (pin "34") (pinfunction "OUTR15_34") (pintype "bidirectional"))
      (node (ref "LED20") (pin "4") (pinfunction "RED_4") (pintype "bidirectional"))
    )
    (net (code "287") (name "/N$LEDR21") (class "Default")
      (node (ref "IC2") (pin "20") (pinfunction "OUTR6_20") (pintype "bidirectional"))
      (node (ref "LED21") (pin "4") (pinfunction "RED_4") (pintype "bidirectional"))
    )
    (net (code "288") (name "/N$LEDR22") (class "Default")
      (node (ref "IC2") (pin "17") (pinfunction "OUTR2_17") (pintype "bidirectional"))
      (node (ref "LED22") (pin "4") (pinfunction "RED_4") (pintype "bidirectional"))
    )
    (net (code "289") (name "/N$LEDR23") (class "Default")
      (node (ref "IC2") (pin "37") (pinfunction "OUTR10_37") (pintype "bidirectional"))
      (node (ref "LED23") (pin "4") (pinfunction "RED_4") (pintype "bidirectional"))
    )
    (net (code "290") (name "/N$LEDR24") (class "Default")
      (node (ref "IC2") (pin "40") (pinfunction "OUTR14_40") (pintype "bidirectional"))
      (node (ref "LED24") (pin "4") (pinfunction "RED_4") (pintype "bidirectional"))
    )
    (net (code "291") (name "/N$LEDR25") (class "Default")
      (node (ref "IC2") (pin "14") (pinfunction "OUTR1_14") (pintype "bidirectional"))
      (node (ref "LED25") (pin "4") (pinfunction "RED_4") (pintype "bidirectional"))
    )
    (net (code "292") (name "/N$LEDR26") (class "Default")
      (node (ref "IC2") (pin "11") (pinfunction "OUTR5_11") (pintype "bidirectional"))
      (node (ref "LED26") (pin "4") (pinfunction "RED_4") (pintype "bidirectional"))
    )
    (net (code "293") (name "/N$LEDR27") (class "Default")
      (node (ref "IC2") (pin "43") (pinfunction "OUTR13_43") (pintype "bidirectional"))
      (node (ref "LED27") (pin "4") (pinfunction "RED_4") (pintype "bidirectional"))
    )
    (net (code "294") (name "/N$LEDR28") (class "Default")
      (node (ref "IC2") (pin "46") (pinfunction "OUTR9_46") (pintype "bidirectional"))
      (node (ref "LED28") (pin "4") (pinfunction "RED_4") (pintype "bidirectional"))
    )
    (net (code "295") (name "/N$LEDR29") (class "Default")
      (node (ref "IC2") (pin "5") (pinfunction "OUTR4_5") (pintype "bidirectional"))
      (node (ref "LED29") (pin "4") (pinfunction "RED_4") (pintype "bidirectional"))
    )
    (net (code "296") (name "/N$LEDR30") (class "Default")
      (node (ref "IC2") (pin "8") (pinfunction "OUTR0_8") (pintype "bidirectional"))
      (node (ref "LED30") (pin "4") (pinfunction "RED_4") (pintype "bidirectional"))
    )
    (net (code "297") (name "/N$LEDR31") (class "Default")
      (node (ref "IC2") (pin "49") (pinfunction "OUTR12_49") (pintype "bidirectional"))
      (node (ref "LED31") (pin "4") (pinfunction "RED_4") (pintype "bidirectional"))
    )
    (net (code "298") (name "/N$LEDR32") (class "Default")
      (node (ref "IC2") (pin "52") (pinfunction "OUTR8_52") (pintype "bidirectional"))
      (node (ref "LED32") (pin "4") (pinfunction "RED_4") (pintype "bidirectional"))
    )
    (net (code "299") (name "/N$LEDR33") (class "Default")
      (node (ref "IC3") (pin "26") (pinfunction "OUTR7_26") (pintype "bidirectional"))
      (node (ref "LED33") (pin "4") (pinfunction "RED_4") (pintype "bidirectional"))
    )
    (net (code "300") (name "/N$LEDR34") (class "Default")
      (node (ref "IC3") (pin "23") (pinfunction "OUTR3_23") (pintype "bidirectional"))
      (node (ref "LED34") (pin "4") (pinfunction "RED_4") (pintype "bidirectional"))
    )
    (net (code "301") (name "/N$LEDR35") (class "Default")
      (node (ref "IC3") (pin "31") (pinfunction "OUTR11_31") (pintype "bidirectional"))
      (node (ref "LED35") (pin "4") (pinfunction "RED_4") (pintype "bidirectional"))
    )
    (net (code "302") (name "/N$LEDR36") (class "Default")
      (node (ref "IC3") (pin "34") (pinfunction "OUTR15_34") (pintype "bidirectional"))
      (node (ref "LED36") (pin "4") (pinfunction "RED_4") (pintype "bidirectional"))
    )
    (net (code "303") (name "/N$LEDR37") (class "Default")
      (node (ref "IC3") (pin "20") (pinfunction "OUTR6_20") (pintype "bidirectional"))
      (node (ref "LED37") (pin "4") (pinfunction "RED_4") (pintype "bidirectional"))
    )
    (net (code "304") (name "/N$LEDR38") (class "Default")
      (node (ref "IC3") (pin "17") (pinfunction "OUTR2_17") (pintype "bidirectional"))
      (node (ref "LED38") (pin "4") (pinfunction "RED_4") (pintype "bidirectional"))
    )
    (net (code "305") (name "/N$LEDR39") (class "Default")
      (node (ref "IC3") (pin "37") (pinfunction "OUTR10_37") (pintype "bidirectional"))
      (node (ref "LED39") (pin "4") (pinfunction "RED_4") (pintype "bidirectional"))
    )
    (net (code "306") (name "/N$LEDR40") (class "Default")
      (node (ref "IC3") (pin "40") (pinfunction "OUTR14_40") (pintype "bidirectional"))
      (node (ref "LED40") (pin "4") (pinfunction "RED_4") (pintype "bidirectional"))
    )
    (net (code "307") (name "/N$LEDR41") (class "Default")
      (node (ref "IC3") (pin "14") (pinfunction "OUTR1_14") (pintype "bidirectional"))
      (node (ref "LED41") (pin "4") (pinfunction "RED_4") (pintype "bidirectional"))
    )
    (net (code "308") (name "/N$LEDR42") (class "Default")
      (node (ref "IC3") (pin "11") (pinfunction "OUTR5_11") (pintype "bidirectional"))
      (node (ref "LED42") (pin "4") (pinfunction "RED_4") (pintype "bidirectional"))
    )
    (net (code "309") (name "/N$LEDR43") (class "Default")
      (node (ref "IC3") (pin "43") (pinfunction "OUTR13_43") (pintype "bidirectional"))
      (node (ref "LED43") (pin "4") (pinfunction "RED_4") (pintype "bidirectional"))
    )
    (net (code "310") (name "/N$LEDR44") (class "Default")
      (node (ref "IC3") (pin "46") (pinfunction "OUTR9_46") (pintype "bidirectional"))
      (node (ref "LED44") (pin "4") (pinfunction "RED_4") (pintype "bidirectional"))
    )
    (net (code "311") (name "/N$LEDR45") (class "Default")
      (node (ref "IC3") (pin "5") (pinfunction "OUTR4_5") (pintype "bidirectional"))
      (node (ref "LED45") (pin "4") (pinfunction "RED_4") (pintype "bidirectional"))
    )
    (net (code "312") (name "/N$LEDR46") (class "Default")
      (node (ref "IC3") (pin "8") (pinfunction "OUTR0_8") (pintype "bidirectional"))
      (node (ref "LED46") (pin "4") (pinfunction "RED_4") (pintype "bidirectional"))
    )
    (net (code "313") (name "/N$LEDR47") (class "Default")
      (node (ref "IC3") (pin "49") (pinfunction "OUTR12_49") (pintype "bidirectional"))
      (node (ref "LED47") (pin "4") (pinfunction "RED_4") (pintype "bidirectional"))
    )
    (net (code "314") (name "/N$LEDR48") (class "Default")
      (node (ref "IC3") (pin "52") (pinfunction "OUTR8_52") (pintype "bidirectional"))
      (node (ref "LED48") (pin "4") (pinfunction "RED_4") (pintype "bidirectional"))
    )
    (net (code "315") (name "/N$LEDR49") (class "Default")
      (node (ref "IC4") (pin "26") (pinfunction "OUTR7_26") (pintype "bidirectional"))
      (node (ref "LED49") (pin "4") (pinfunction "RED_4") (pintype "bidirectional"))
    )
    (net (code "316") (name "/N$LEDR50") (class "Default")
      (node (ref "IC4") (pin "23") (pinfunction "OUTR3_23") (pintype "bidirectional"))
      (node (ref "LED50") (pin "4") (pinfunction "RED_4") (pintype "bidirectional"))
    )
    (net (code "317") (name "/N$LEDR51") (class "Default")
      (node (ref "IC4") (pin "31") (pinfunction "OUTR11_31") (pintype "bidirectional"))
      (node (ref "LED51") (pin "4") (pinfunction "RED_4") (pintype "bidirectional"))
    )
    (net (code "318") (name "/N$LEDR52") (class "Default")
      (node (ref "IC4") (pin "34") (pinfunction "OUTR15_34") (pintype "bidirectional"))
      (node (ref "LED52") (pin "4") (pinfunction "RED_4") (pintype "bidirectional"))
    )
    (net (code "319") (name "/N$LEDR53") (class "Default")
      (node (ref "IC4") (pin "20") (pinfunction "OUTR6_20") (pintype "bidirectional"))
      (node (ref "LED53") (pin "4") (pinfunction "RED_4") (pintype "bidirectional"))
    )
    (net (code "320") (name "/N$LEDR54") (class "Default")
      (node (ref "IC4") (pin "17") (pinfunction "OUTR2_17") (pintype "bidirectional"))
      (node (ref "LED54") (pin "4") (pinfunction "RED_4") (pintype "bidirectional"))
    )
    (net (code "321") (name "/N$LEDR55") (class "Default")
      (node (ref "IC4") (pin "37") (pinfunction "OUTR10_37") (pintype "bidirectional"))
      (node (ref "LED55") (pin "4") (pinfunction "RED_4") (pintype "bidirectional"))
    )
    (net (code "322") (name "/N$LEDR56") (class "Default")
      (node (ref "IC4") (pin "40") (pinfunction "OUTR14_40") (pintype "bidirectional"))
      (node (ref "LED56") (pin "4") (pinfunction "RED_4") (pintype "bidirectional"))
    )
    (net (code "323") (name "/N$LEDR57") (class "Default")
      (node (ref "IC4") (pin "14") (pinfunction "OUTR1_14") (pintype "bidirectional"))
      (node (ref "LED57") (pin "4") (pinfunction "RED_4") (pintype "bidirectional"))
    )
    (net (code "324") (name "/N$LEDR58") (class "Default")
      (node (ref "IC4") (pin "11") (pinfunction "OUTR5_11") (pintype "bidirectional"))
      (node (ref "LED58") (pin "4") (pinfunction "RED_4") (pintype "bidirectional"))
    )
    (net (code "325") (name "/N$LEDR59") (class "Default")
      (node (ref "IC4") (pin "43") (pinfunction "OUTR13_43") (pintype "bidirectional"))
      (node (ref "LED59") (pin "4") (pinfunction "RED_4") (pintype "bidirectional"))
    )
    (net (code "326") (name "/N$LEDR60") (class "Default")
      (node (ref "IC4") (pin "46") (pinfunction "OUTR9_46") (pintype "bidirectional"))
      (node (ref "LED60") (pin "4") (pinfunction "RED_4") (pintype "bidirectional"))
    )
    (net (code "327") (name "/N$LEDR61") (class "Default")
      (node (ref "IC4") (pin "5") (pinfunction "OUTR4_5") (pintype "bidirectional"))
      (node (ref "LED61") (pin "4") (pinfunction "RED_4") (pintype "bidirectional"))
    )
    (net (code "328") (name "/N$LEDR62") (class "Default")
      (node (ref "IC4") (pin "8") (pinfunction "OUTR0_8") (pintype "bidirectional"))
      (node (ref "LED62") (pin "4") (pinfunction "RED_4") (pintype "bidirectional"))
    )
    (net (code "329") (name "/N$LEDR63") (class "Default")
      (node (ref "IC4") (pin "49") (pinfunction "OUTR12_49") (pintype "bidirectional"))
      (node (ref "LED63") (pin "4") (pinfunction "RED_4") (pintype "bidirectional"))
    )
    (net (code "330") (name "/N$LEDR64") (class "Default")
      (node (ref "IC4") (pin "52") (pinfunction "OUTR8_52") (pintype "bidirectional"))
      (node (ref "LED64") (pin "4") (pinfunction "RED_4") (pintype "bidirectional"))
    )
    (net (code "331") (name "/N$LEDR65") (class "Default")
      (node (ref "IC5") (pin "26") (pinfunction "OUTR7_26") (pintype "bidirectional"))
      (node (ref "LED65") (pin "4") (pinfunction "RED_4") (pintype "bidirectional"))
    )
    (net (code "332") (name "/N$LEDR66") (class "Default")
      (node (ref "IC5") (pin "23") (pinfunction "OUTR3_23") (pintype "bidirectional"))
      (node (ref "LED66") (pin "4") (pinfunction "RED_4") (pintype "bidirectional"))
    )
    (net (code "333") (name "/N$LEDR67") (class "Default")
      (node (ref "IC5") (pin "31") (pinfunction "OUTR11_31") (pintype "bidirectional"))
      (node (ref "LED67") (pin "4") (pinfunction "RED_4") (pintype "bidirectional"))
    )
    (net (code "334") (name "/N$LEDR68") (class "Default")
      (node (ref "IC5") (pin "34") (pinfunction "OUTR15_34") (pintype "bidirectional"))
      (node (ref "LED68") (pin "4") (pinfunction "RED_4") (pintype "bidirectional"))
    )
    (net (code "335") (name "/N$LEDR69") (class "Default")
      (node (ref "IC5") (pin "20") (pinfunction "OUTR6_20") (pintype "bidirectional"))
      (node (ref "LED69") (pin "4") (pinfunction "RED_4") (pintype "bidirectional"))
    )
    (net (code "336") (name "/N$LEDR70") (class "Default")
      (node (ref "IC5") (pin "17") (pinfunction "OUTR2_17") (pintype "bidirectional"))
      (node (ref "LED70") (pin "4") (pinfunction "RED_4") (pintype "bidirectional"))
    )
    (net (code "337") (name "/N$LEDR71") (class "Default")
      (node (ref "IC5") (pin "37") (pinfunction "OUTR10_37") (pintype "bidirectional"))
      (node (ref "LED71") (pin "4") (pinfunction "RED_4") (pintype "bidirectional"))
    )
    (net (code "338") (name "/N$LEDR72") (class "Default")
      (node (ref "IC5") (pin "40") (pinfunction "OUTR14_40") (pintype "bidirectional"))
      (node (ref "LED72") (pin "4") (pinfunction "RED_4") (pintype "bidirectional"))
    )
    (net (code "339") (name "/N$LEDR73") (class "Default")
      (node (ref "IC5") (pin "14") (pinfunction "OUTR1_14") (pintype "bidirectional"))
      (node (ref "LED73") (pin "4") (pinfunction "RED_4") (pintype "bidirectional"))
    )
    (net (code "340") (name "/N$LEDR74") (class "Default")
      (node (ref "IC5") (pin "11") (pinfunction "OUTR5_11") (pintype "bidirectional"))
      (node (ref "LED74") (pin "4") (pinfunction "RED_4") (pintype "bidirectional"))
    )
    (net (code "341") (name "/N$LEDR75") (class "Default")
      (node (ref "IC5") (pin "43") (pinfunction "OUTR13_43") (pintype "bidirectional"))
      (node (ref "LED75") (pin "4") (pinfunction "RED_4") (pintype "bidirectional"))
    )
    (net (code "342") (name "/N$LEDR76") (class "Default")
      (node (ref "IC5") (pin "46") (pinfunction "OUTR9_46") (pintype "bidirectional"))
      (node (ref "LED76") (pin "4") (pinfunction "RED_4") (pintype "bidirectional"))
    )
    (net (code "343") (name "/N$LEDR77") (class "Default")
      (node (ref "IC5") (pin "5") (pinfunction "OUTR4_5") (pintype "bidirectional"))
      (node (ref "LED77") (pin "4") (pinfunction "RED_4") (pintype "bidirectional"))
    )
    (net (code "344") (name "/N$LEDR78") (class "Default")
      (node (ref "IC5") (pin "8") (pinfunction "OUTR0_8") (pintype "bidirectional"))
      (node (ref "LED78") (pin "4") (pinfunction "RED_4") (pintype "bidirectional"))
    )
    (net (code "345") (name "/N$LEDR79") (class "Default")
      (node (ref "IC5") (pin "49") (pinfunction "OUTR12_49") (pintype "bidirectional"))
      (node (ref "LED79") (pin "4") (pinfunction "RED_4") (pintype "bidirectional"))
    )
    (net (code "346") (name "/N$LEDR80") (class "Default")
      (node (ref "IC5") (pin "52") (pinfunction "OUTR8_52") (pintype "bidirectional"))
      (node (ref "LED80") (pin "4") (pinfunction "RED_4") (pintype "bidirectional"))
    )
    (net (code "347") (name "/N$LEDR81") (class "Default")
      (node (ref "IC6") (pin "26") (pinfunction "OUTR7_26") (pintype "bidirectional"))
      (node (ref "LED81") (pin "4") (pinfunction "RED_4") (pintype "bidirectional"))
    )
    (net (code "348") (name "/N$LEDR82") (class "Default")
      (node (ref "IC6") (pin "23") (pinfunction "OUTR3_23") (pintype "bidirectional"))
      (node (ref "LED82") (pin "4") (pinfunction "RED_4") (pintype "bidirectional"))
    )
    (net (code "349") (name "/N$LEDR83") (class "Default")
      (node (ref "IC6") (pin "31") (pinfunction "OUTR11_31") (pintype "bidirectional"))
      (node (ref "LED83") (pin "4") (pinfunction "RED_4") (pintype "bidirectional"))
    )
    (net (code "350") (name "/N$LEDR84") (class "Default")
      (node (ref "IC6") (pin "34") (pinfunction "OUTR15_34") (pintype "bidirectional"))
      (node (ref "LED84") (pin "4") (pinfunction "RED_4") (pintype "bidirectional"))
    )
    (net (code "351") (name "/N$LEDR85") (class "Default")
      (node (ref "IC6") (pin "20") (pinfunction "OUTR6_20") (pintype "bidirectional"))
      (node (ref "LED85") (pin "4") (pinfunction "RED_4") (pintype "bidirectional"))
    )
    (net (code "352") (name "/N$LEDR86") (class "Default")
      (node (ref "IC6") (pin "17") (pinfunction "OUTR2_17") (pintype "bidirectional"))
      (node (ref "LED86") (pin "4") (pinfunction "RED_4") (pintype "bidirectional"))
    )
    (net (code "353") (name "/N$LEDR87") (class "Default")
      (node (ref "IC6") (pin "37") (pinfunction "OUTR10_37") (pintype "bidirectional"))
      (node (ref "LED87") (pin "4") (pinfunction "RED_4") (pintype "bidirectional"))
    )
    (net (code "354") (name "/N$LEDR88") (class "Default")
      (node (ref "IC6") (pin "40") (pinfunction "OUTR14_40") (pintype "bidirectional"))
      (node (ref "LED88") (pin "4") (pinfunction "RED_4") (pintype "bidirectional"))
    )
    (net (code "355") (name "/N$LEDR89") (class "Default")
      (node (ref "IC6") (pin "14") (pinfunction "OUTR1_14") (pintype "bidirectional"))
      (node (ref "LED89") (pin "4") (pinfunction "RED_4") (pintype "bidirectional"))
    )
    (net (code "356") (name "/N$LEDR90") (class "Default")
      (node (ref "IC6") (pin "11") (pinfunction "OUTR5_11") (pintype "bidirectional"))
      (node (ref "LED90") (pin "4") (pinfunction "RED_4") (pintype "bidirectional"))
    )
    (net (code "357") (name "/N$LEDR91") (class "Default")
      (node (ref "IC6") (pin "43") (pinfunction "OUTR13_43") (pintype "bidirectional"))
      (node (ref "LED91") (pin "4") (pinfunction "RED_4") (pintype "bidirectional"))
    )
    (net (code "358") (name "/N$LEDR92") (class "Default")
      (node (ref "IC6") (pin "46") (pinfunction "OUTR9_46") (pintype "bidirectional"))
      (node (ref "LED92") (pin "4") (pinfunction "RED_4") (pintype "bidirectional"))
    )
    (net (code "359") (name "/N$LEDR93") (class "Default")
      (node (ref "IC6") (pin "5") (pinfunction "OUTR4_5") (pintype "bidirectional"))
      (node (ref "LED93") (pin "4") (pinfunction "RED_4") (pintype "bidirectional"))
    )
    (net (code "360") (name "/N$LEDR94") (class "Default")
      (node (ref "IC6") (pin "8") (pinfunction "OUTR0_8") (pintype "bidirectional"))
      (node (ref "LED94") (pin "4") (pinfunction "RED_4") (pintype "bidirectional"))
    )
    (net (code "361") (name "/N$LEDR95") (class "Default")
      (node (ref "IC6") (pin "49") (pinfunction "OUTR12_49") (pintype "bidirectional"))
      (node (ref "LED95") (pin "4") (pinfunction "RED_4") (pintype "bidirectional"))
    )
    (net (code "362") (name "/N$LEDR96") (class "Default")
      (node (ref "IC6") (pin "52") (pinfunction "OUTR8_52") (pintype "bidirectional"))
      (node (ref "LED96") (pin "4") (pinfunction "RED_4") (pintype "bidirectional"))
    )
    (net (code "363") (name "/N$LEDR97") (class "Default")
      (node (ref "IC7") (pin "26") (pinfunction "OUTR7_26") (pintype "bidirectional"))
      (node (ref "LED97") (pin "4") (pinfunction "RED_4") (pintype "bidirectional"))
    )
    (net (code "364") (name "/N$LEDR98") (class "Default")
      (node (ref "IC7") (pin "23") (pinfunction "OUTR3_23") (pintype "bidirectional"))
      (node (ref "LED98") (pin "4") (pinfunction "RED_4") (pintype "bidirectional"))
    )
    (net (code "365") (name "/N$LEDR99") (class "Default")
      (node (ref "IC7") (pin "31") (pinfunction "OUTR11_31") (pintype "bidirectional"))
      (node (ref "LED99") (pin "4") (pinfunction "RED_4") (pintype "bidirectional"))
    )
    (net (code "366") (name "/N$LEDR100") (class "Default")
      (node (ref "IC7") (pin "34") (pinfunction "OUTR15_34") (pintype "bidirectional"))
      (node (ref "LED100") (pin "4") (pinfunction "RED_4") (pintype "bidirectional"))
    )
    (net (code "367") (name "/N$LEDR101") (class "Default")
      (node (ref "IC7") (pin "20") (pinfunction "OUTR6_20") (pintype "bidirectional"))
      (node (ref "LED101") (pin "4") (pinfunction "RED_4") (pintype "bidirectional"))
    )
    (net (code "368") (name "/N$LEDR102") (class "Default")
      (node (ref "IC7") (pin "17") (pinfunction "OUTR2_17") (pintype "bidirectional"))
      (node (ref "LED102") (pin "4") (pinfunction "RED_4") (pintype "bidirectional"))
    )
    (net (code "369") (name "/N$LEDR103") (class "Default")
      (node (ref "IC7") (pin "37") (pinfunction "OUTR10_37") (pintype "bidirectional"))
      (node (ref "LED103") (pin "4") (pinfunction "RED_4") (pintype "bidirectional"))
    )
    (net (code "370") (name "/N$LEDR104") (class "Default")
      (node (ref "IC7") (pin "40") (pinfunction "OUTR14_40") (pintype "bidirectional"))
      (node (ref "LED104") (pin "4") (pinfunction "RED_4") (pintype "bidirectional"))
    )
    (net (code "371") (name "/N$LEDR105") (class "Default")
      (node (ref "IC7") (pin "14") (pinfunction "OUTR1_14") (pintype "bidirectional"))
      (node (ref "LED105") (pin "4") (pinfunction "RED_4") (pintype "bidirectional"))
    )
    (net (code "372") (name "/N$LEDR106") (class "Default")
      (node (ref "IC7") (pin "11") (pinfunction "OUTR5_11") (pintype "bidirectional"))
      (node (ref "LED106") (pin "4") (pinfunction "RED_4") (pintype "bidirectional"))
    )
    (net (code "373") (name "/N$LEDR107") (class "Default")
      (node (ref "IC7") (pin "43") (pinfunction "OUTR13_43") (pintype "bidirectional"))
      (node (ref "LED107") (pin "4") (pinfunction "RED_4") (pintype "bidirectional"))
    )
    (net (code "374") (name "/N$LEDR108") (class "Default")
      (node (ref "IC7") (pin "46") (pinfunction "OUTR9_46") (pintype "bidirectional"))
      (node (ref "LED108") (pin "4") (pinfunction "RED_4") (pintype "bidirectional"))
    )
    (net (code "375") (name "/N$LEDR109") (class "Default")
      (node (ref "IC7") (pin "5") (pinfunction "OUTR4_5") (pintype "bidirectional"))
      (node (ref "LED109") (pin "4") (pinfunction "RED_4") (pintype "bidirectional"))
    )
    (net (code "376") (name "/N$LEDR110") (class "Default")
      (node (ref "IC7") (pin "8") (pinfunction "OUTR0_8") (pintype "bidirectional"))
      (node (ref "LED110") (pin "4") (pinfunction "RED_4") (pintype "bidirectional"))
    )
    (net (code "377") (name "/N$LEDR111") (class "Default")
      (node (ref "IC7") (pin "49") (pinfunction "OUTR12_49") (pintype "bidirectional"))
      (node (ref "LED111") (pin "4") (pinfunction "RED_4") (pintype "bidirectional"))
    )
    (net (code "378") (name "/N$LEDR112") (class "Default")
      (node (ref "IC7") (pin "52") (pinfunction "OUTR8_52") (pintype "bidirectional"))
      (node (ref "LED112") (pin "4") (pinfunction "RED_4") (pintype "bidirectional"))
    )
    (net (code "379") (name "/N$LEDR113") (class "Default")
      (node (ref "IC8") (pin "26") (pinfunction "OUTR7_26") (pintype "bidirectional"))
      (node (ref "LED113") (pin "4") (pinfunction "RED_4") (pintype "bidirectional"))
    )
    (net (code "380") (name "/N$LEDR114") (class "Default")
      (node (ref "IC8") (pin "23") (pinfunction "OUTR3_23") (pintype "bidirectional"))
      (node (ref "LED114") (pin "4") (pinfunction "RED_4") (pintype "bidirectional"))
    )
    (net (code "381") (name "/N$LEDR115") (class "Default")
      (node (ref "IC8") (pin "31") (pinfunction "OUTR11_31") (pintype "bidirectional"))
      (node (ref "LED115") (pin "4") (pinfunction "RED_4") (pintype "bidirectional"))
    )
    (net (code "382") (name "/N$LEDR116") (class "Default")
      (node (ref "IC8") (pin "34") (pinfunction "OUTR15_34") (pintype "bidirectional"))
      (node (ref "LED116") (pin "4") (pinfunction "RED_4") (pintype "bidirectional"))
    )
    (net (code "383") (name "/N$LEDR117") (class "Default")
      (node (ref "IC8") (pin "20") (pinfunction "OUTR6_20") (pintype "bidirectional"))
      (node (ref "LED117") (pin "4") (pinfunction "RED_4") (pintype "bidirectional"))
    )
    (net (code "384") (name "/N$LEDR118") (class "Default")
      (node (ref "IC8") (pin "17") (pinfunction "OUTR2_17") (pintype "bidirectional"))
      (node (ref "LED118") (pin "4") (pinfunction "RED_4") (pintype "bidirectional"))
    )
    (net (code "385") (name "/N$LEDR119") (class "Default")
      (node (ref "IC8") (pin "37") (pinfunction "OUTR10_37") (pintype "bidirectional"))
      (node (ref "LED119") (pin "4") (pinfunction "RED_4") (pintype "bidirectional"))
    )
    (net (code "386") (name "/N$LEDR120") (class "Default")
      (node (ref "IC8") (pin "40") (pinfunction "OUTR14_40") (pintype "bidirectional"))
      (node (ref "LED120") (pin "4") (pinfunction "RED_4") (pintype "bidirectional"))
    )
    (net (code "387") (name "/SIN_1,2") (class "Default")
      (node (ref "IC2") (pin "1") (pinfunction "SIN_1") (pintype "bidirectional"))
      (node (ref "SV1") (pin "12") (pinfunction "12_12") (pintype "passive"))
    )
    (net (code "388") (name "/SIN_3,4") (class "Default")
      (node (ref "IC4") (pin "1") (pinfunction "SIN_1") (pintype "bidirectional"))
      (node (ref "SV1") (pin "11") (pinfunction "11_11") (pintype "passive"))
    )
    (net (code "389") (name "/SIN_5,6") (class "Default")
      (node (ref "IC6") (pin "1") (pinfunction "SIN_1") (pintype "bidirectional"))
      (node (ref "SV1") (pin "10") (pinfunction "10_10") (pintype "passive"))
    )
    (net (code "390") (name "/SIN_7,8") (class "Default")
      (node (ref "IC8") (pin "1") (pinfunction "SIN_1") (pintype "bidirectional"))
      (node (ref "SV1") (pin "9") (pinfunction "9_9") (pintype "passive"))
    )
    (net (code "391") (name "/SOUT1") (class "Default")
      (node (ref "IC1") (pin "28") (pinfunction "SOUT_28") (pintype "bidirectional"))
    )
    (net (code "392") (name "/SOUT2") (class "Default")
      (node (ref "IC1") (pin "1") (pinfunction "SIN_1") (pintype "bidirectional"))
      (node (ref "IC2") (pin "28") (pinfunction "SOUT_28") (pintype "bidirectional"))
    )
    (net (code "393") (name "/SOUT3") (class "Default")
      (node (ref "IC3") (pin "28") (pinfunction "SOUT_28") (pintype "bidirectional"))
    )
    (net (code "394") (name "/SOUT4") (class "Default")
      (node (ref "IC3") (pin "1") (pinfunction "SIN_1") (pintype "bidirectional"))
      (node (ref "IC4") (pin "28") (pinfunction "SOUT_28") (pintype "bidirectional"))
    )
    (net (code "395") (name "/SOUT5") (class "Default")
      (node (ref "IC5") (pin "28") (pinfunction "SOUT_28") (pintype "bidirectional"))
    )
    (net (code "396") (name "/SOUT6") (class "Default")
      (node (ref "IC5") (pin "1") (pinfunction "SIN_1") (pintype "bidirectional"))
      (node (ref "IC6") (pin "28") (pinfunction "SOUT_28") (pintype "bidirectional"))
    )
    (net (code "397") (name "/SOUT7") (class "Default")
      (node (ref "IC7") (pin "28") (pinfunction "SOUT_28") (pintype "bidirectional"))
    )
    (net (code "398") (name "/SOUT8") (class "Default")
      (node (ref "IC7") (pin "1") (pinfunction "SIN_1") (pintype "bidirectional"))
      (node (ref "IC8") (pin "28") (pinfunction "SOUT_28") (pintype "bidirectional"))
    )
    (net (code "399") (name "3V3_LOGIC") (class "Default")
      (node (ref "C1") (pin "1") (pinfunction "1_1") (pintype "passive"))
      (node (ref "C1B") (pin "1") (pinfunction "1_1") (pintype "passive"))
      (node (ref "C2") (pin "1") (pinfunction "1_1") (pintype "passive"))
      (node (ref "C28") (pin "1") (pinfunction "1_1") (pintype "passive"))
      (node (ref "C29") (pin "1") (pinfunction "1_1") (pintype "passive"))
      (node (ref "C2B") (pin "1") (pinfunction "1_1") (pintype "passive"))
      (node (ref "C3") (pin "1") (pinfunction "1_1") (pintype "passive"))
      (node (ref "C30") (pin "1") (pinfunction "1_1") (pintype "passive"))
      (node (ref "C31") (pin "1") (pinfunction "1_1") (pintype "passive"))
      (node (ref "C32") (pin "1") (pinfunction "1_1") (pintype "passive"))
      (node (ref "C33") (pin "1") (pinfunction "1_1") (pintype "passive"))
      (node (ref "C3B") (pin "1") (pinfunction "1_1") (pintype "passive"))
      (node (ref "C4") (pin "1") (pinfunction "1_1") (pintype "passive"))
      (node (ref "C4B") (pin "1") (pinfunction "1_1") (pintype "passive"))
      (node (ref "C5") (pin "1") (pinfunction "1_1") (pintype "passive"))
      (node (ref "C5B") (pin "1") (pinfunction "1_1") (pintype "passive"))
      (node (ref "C6") (pin "1") (pinfunction "1_1") (pintype "passive"))
      (node (ref "C6B") (pin "1") (pinfunction "1_1") (pintype "passive"))
      (node (ref "C7") (pin "1") (pinfunction "1_1") (pintype "passive"))
      (node (ref "C7B") (pin "1") (pinfunction "1_1") (pintype "passive"))
      (node (ref "C8") (pin "1") (pinfunction "1_1") (pintype "passive"))
      (node (ref "C8B") (pin "1") (pinfunction "1_1") (pintype "passive"))
      (node (ref "IC1") (pin "54") (pinfunction "VCC_54") (pintype "bidirectional"))
      (node (ref "IC10") (pin "5") (pinfunction "VCC_5") (pintype "bidirectional"))
      (node (ref "IC11") (pin "5") (pinfunction "VCC_5") (pintype "bidirectional"))
      (node (ref "IC2") (pin "54") (pinfunction "VCC_54") (pintype "bidirectional"))
      (node (ref "IC3") (pin "54") (pinfunction "VCC_54") (pintype "bidirectional"))
      (node (ref "IC4") (pin "54") (pinfunction "VCC_54") (pintype "bidirectional"))
      (node (ref "IC5") (pin "54") (pinfunction "VCC_54") (pintype "bidirectional"))
      (node (ref "IC6") (pin "54") (pinfunction "VCC_54") (pintype "bidirectional"))
      (node (ref "IC7") (pin "54") (pinfunction "VCC_54") (pintype "bidirectional"))
      (node (ref "IC8") (pin "54") (pinfunction "VCC_54") (pintype "bidirectional"))
      (node (ref "IC9") (pin "5") (pinfunction "VCC_5") (pintype "bidirectional"))
      (node (ref "SV1") (pin "1") (pinfunction "1_1") (pintype "passive"))
    )
    (net (code "400") (name "GSCLK") (class "Default")
      (node (ref "IC1") (pin "55") (pinfunction "GSCLK_55") (pintype "bidirectional"))
      (node (ref "IC11") (pin "4") (pinfunction "Y_4") (pintype "bidirectional"))
      (node (ref "IC2") (pin "55") (pinfunction "GSCLK_55") (pintype "bidirectional"))
      (node (ref "IC3") (pin "55") (pinfunction "GSCLK_55") (pintype "bidirectional"))
      (node (ref "IC4") (pin "55") (pinfunction "GSCLK_55") (pintype "bidirectional"))
      (node (ref "IC5") (pin "55") (pinfunction "GSCLK_55") (pintype "bidirectional"))
      (node (ref "IC6") (pin "55") (pinfunction "GSCLK_55") (pintype "bidirectional"))
      (node (ref "IC7") (pin "55") (pinfunction "GSCLK_55") (pintype "bidirectional"))
      (node (ref "IC8") (pin "55") (pinfunction "GSCLK_55") (pintype "bidirectional"))
    )
    (net (code "401") (name "GSCLK_FPGA") (class "Default")
      (node (ref "IC11") (pin "2") (pinfunction "A_2") (pintype "bidirectional"))
      (node (ref "SV1") (pin "3") (pinfunction "3_3") (pintype "passive"))
    )
    (net (code "402") (name "LAT") (class "Default")
      (node (ref "IC1") (pin "3") (pinfunction "LAT_3") (pintype "bidirectional"))
      (node (ref "IC2") (pin "3") (pinfunction "LAT_3") (pintype "bidirectional"))
      (node (ref "IC3") (pin "3") (pinfunction "LAT_3") (pintype "bidirectional"))
      (node (ref "IC4") (pin "3") (pinfunction "LAT_3") (pintype "bidirectional"))
      (node (ref "IC5") (pin "3") (pinfunction "LAT_3") (pintype "bidirectional"))
      (node (ref "IC6") (pin "3") (pinfunction "LAT_3") (pintype "bidirectional"))
      (node (ref "IC7") (pin "3") (pinfunction "LAT_3") (pintype "bidirectional"))
      (node (ref "IC8") (pin "3") (pinfunction "LAT_3") (pintype "bidirectional"))
      (node (ref "IC9") (pin "4") (pinfunction "Y_4") (pintype "bidirectional"))
    )
    (net (code "403") (name "LAT_FPGA") (class "Default")
      (node (ref "IC9") (pin "2") (pinfunction "A_2") (pintype "bidirectional"))
      (node (ref "SV1") (pin "5") (pinfunction "5_5") (pintype "passive"))
    )
    (net (code "404") (name "SCLK") (class "Default")
      (node (ref "IC1") (pin "2") (pinfunction "SCLK_2") (pintype "bidirectional"))
      (node (ref "IC10") (pin "4") (pinfunction "Y_4") (pintype "bidirectional"))
      (node (ref "IC2") (pin "2") (pinfunction "SCLK_2") (pintype "bidirectional"))
      (node (ref "IC3") (pin "2") (pinfunction "SCLK_2") (pintype "bidirectional"))
      (node (ref "IC4") (pin "2") (pinfunction "SCLK_2") (pintype "bidirectional"))
      (node (ref "IC5") (pin "2") (pinfunction "SCLK_2") (pintype "bidirectional"))
      (node (ref "IC6") (pin "2") (pinfunction "SCLK_2") (pintype "bidirectional"))
      (node (ref "IC7") (pin "2") (pinfunction "SCLK_2") (pintype "bidirectional"))
      (node (ref "IC8") (pin "2") (pinfunction "SCLK_2") (pintype "bidirectional"))
    )
    (net (code "405") (name "SCLK_FPGA") (class "Default")
      (node (ref "IC10") (pin "2") (pinfunction "A_2") (pintype "bidirectional"))
      (node (ref "SV1") (pin "7") (pinfunction "7_7") (pintype "passive"))
    )
    (net (code "406") (name "unconnected-(IC9-N.C.-Pad1)") (class "Default")
      (node (ref "IC9") (pin "1") (pinfunction "N.C._1") (pintype "no_connect"))
    )
    (net (code "407") (name "unconnected-(IC10-N.C.-Pad1)") (class "Default")
      (node (ref "IC10") (pin "1") (pinfunction "N.C._1") (pintype "no_connect"))
    )
    (net (code "408") (name "unconnected-(IC11-N.C.-Pad1)") (class "Default")
      (node (ref "IC11") (pin "1") (pinfunction "N.C._1") (pintype "no_connect"))
    )
  )
)
